# skyrizz_e32__se050-v1_1.net
KiCad netlist of a schematic drawn in EasyEDA Pro
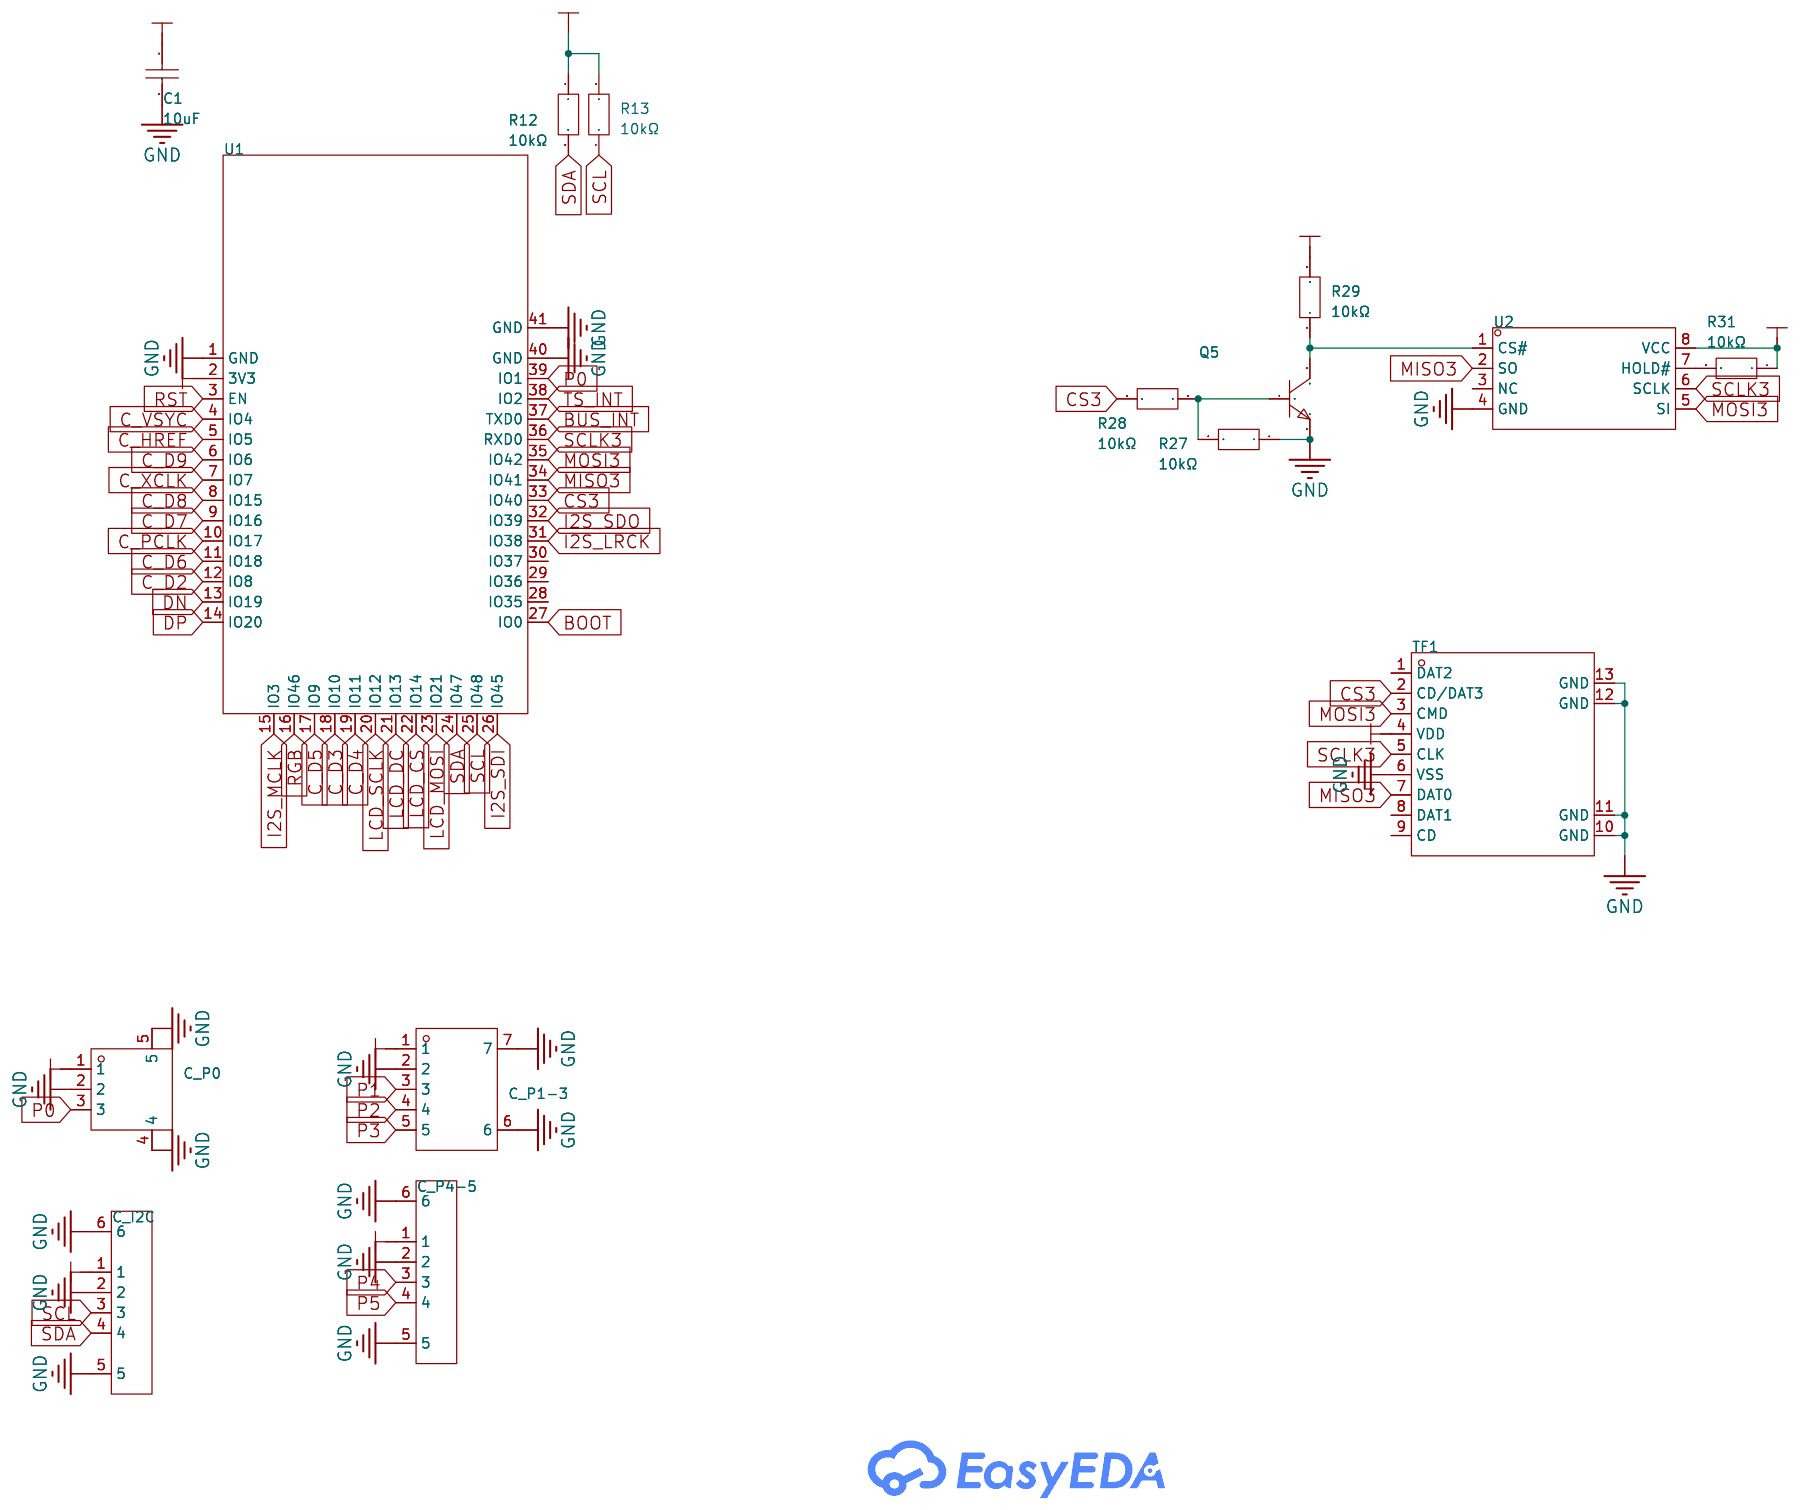
[diagram p0: MCU & MEMORY]
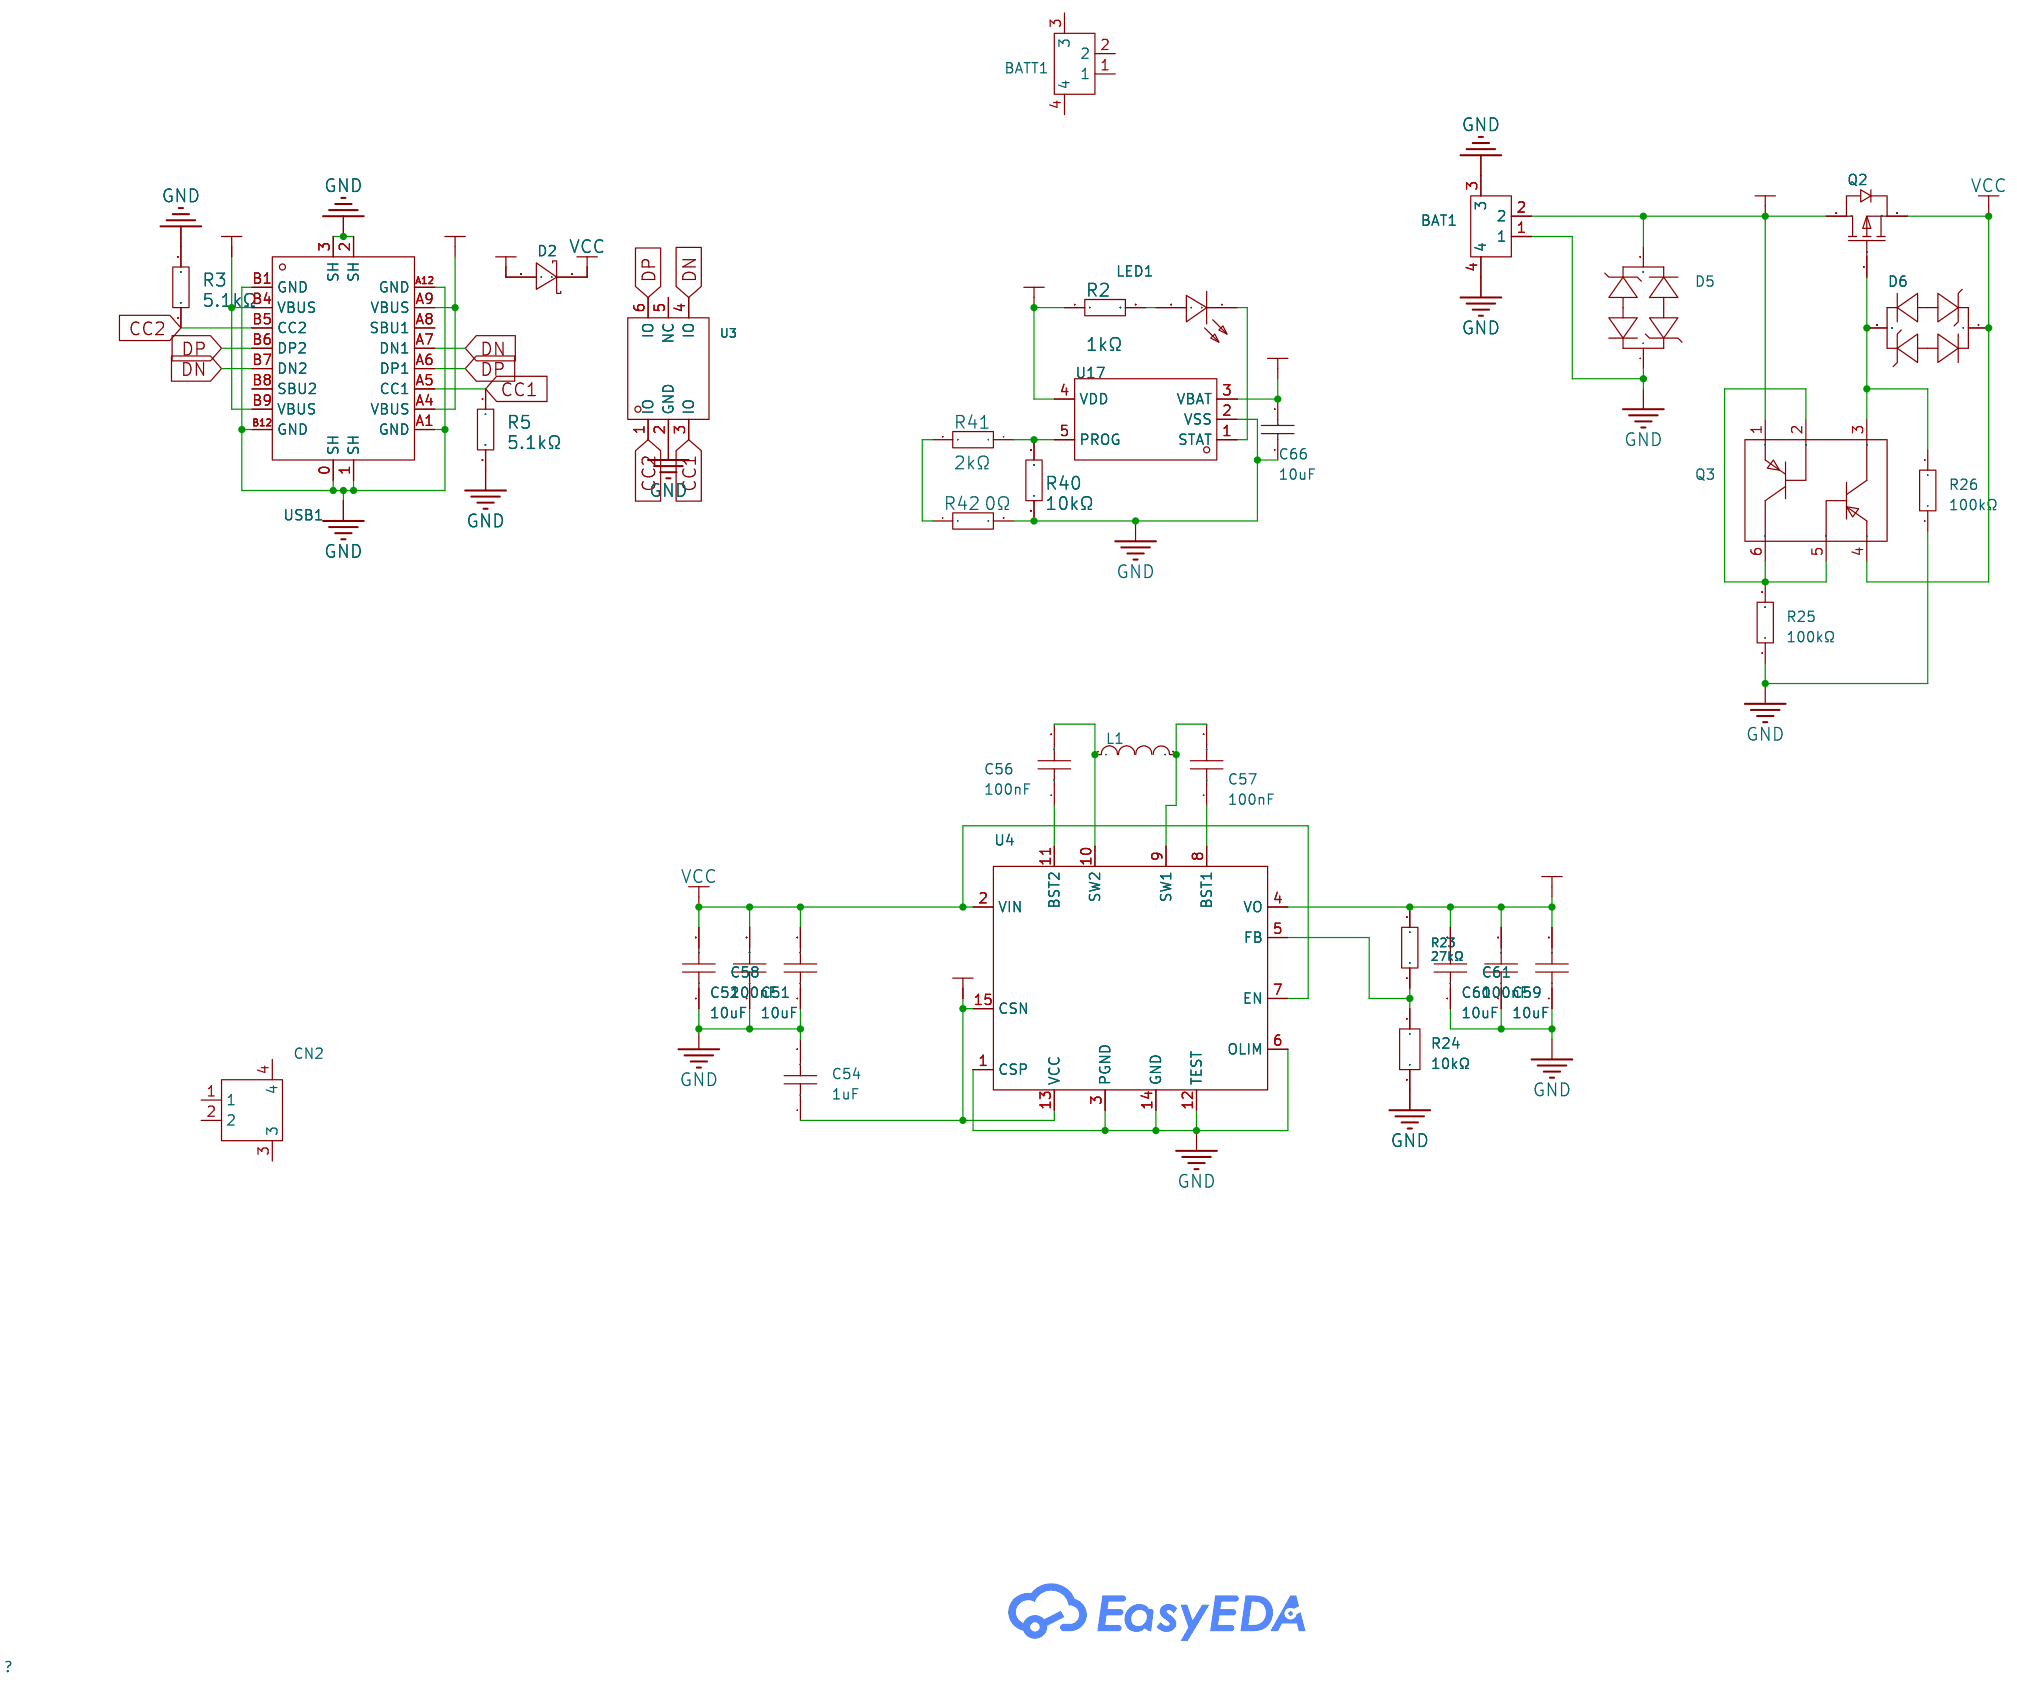
[diagram p1: POWER]
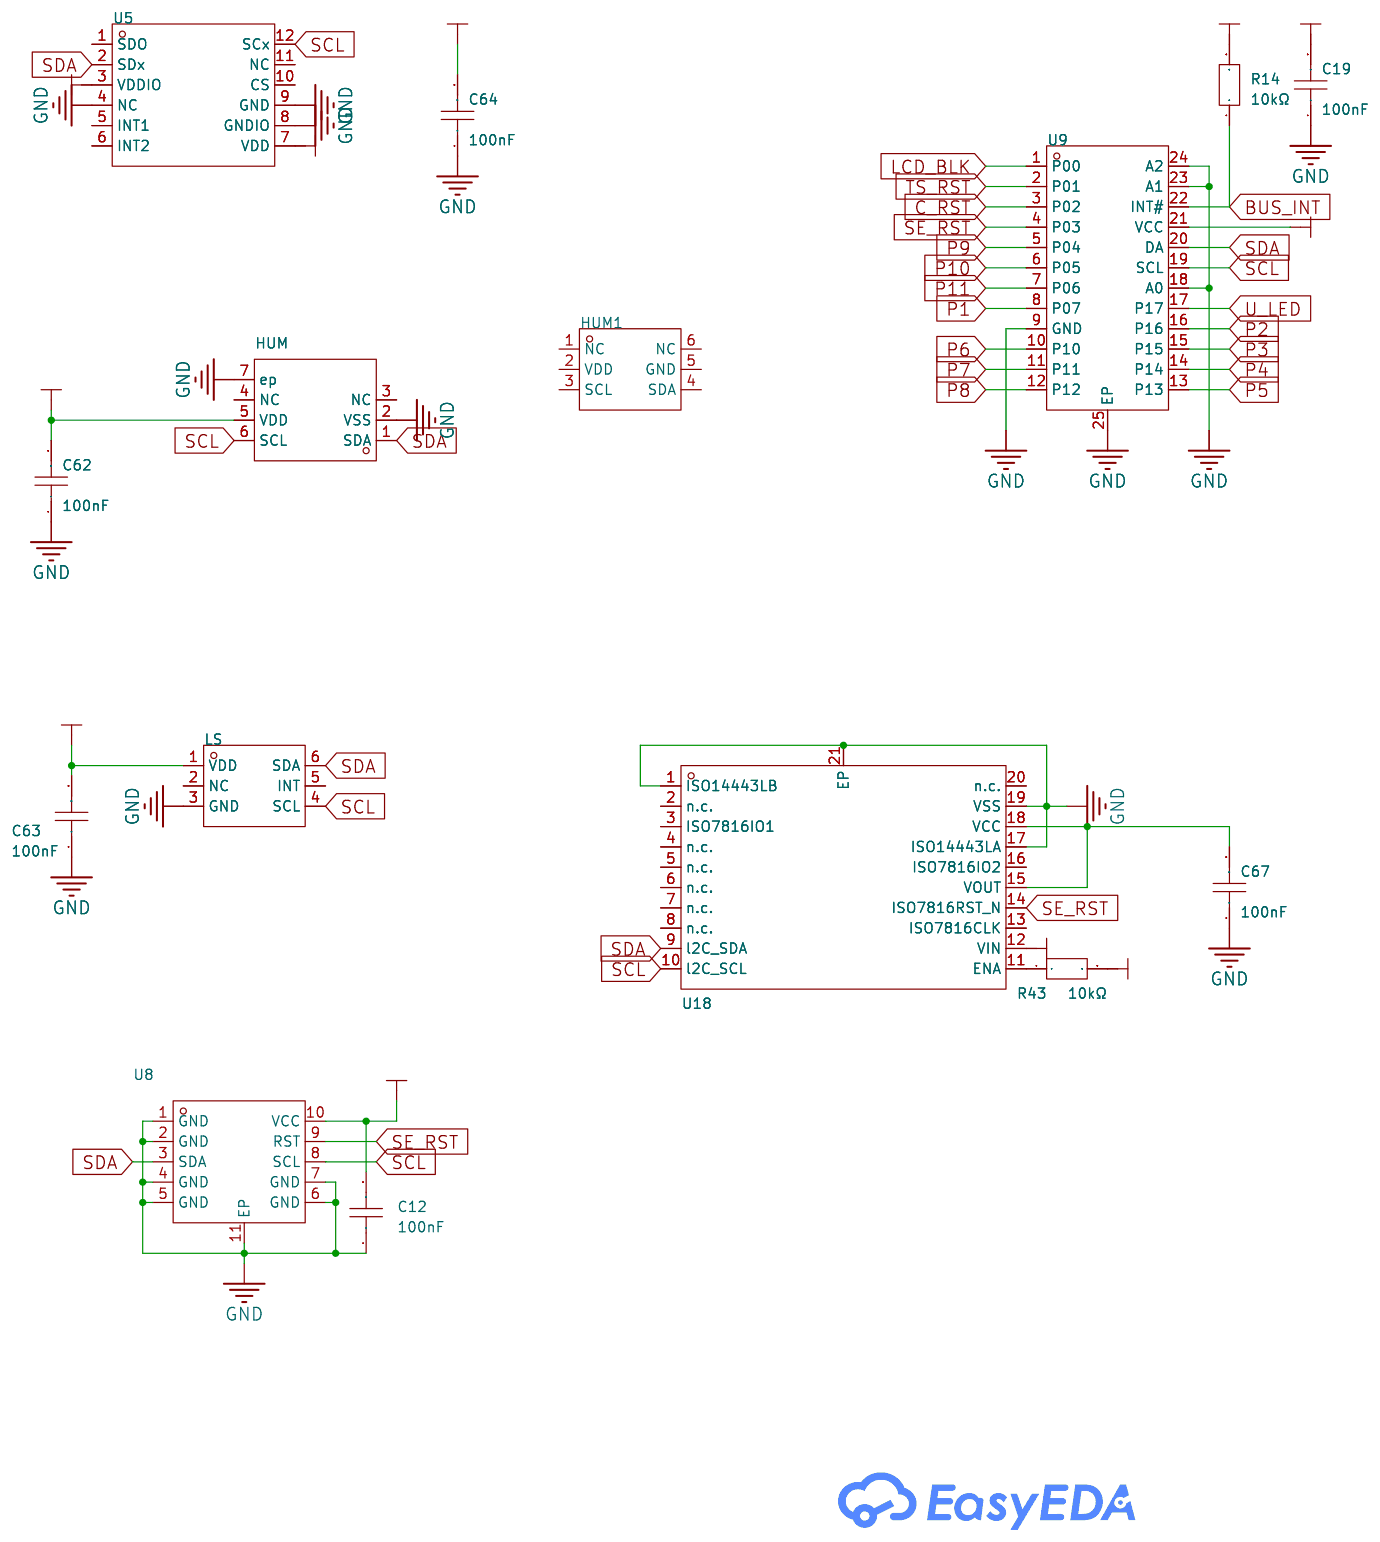
[diagram p2: SENSOR I2C]
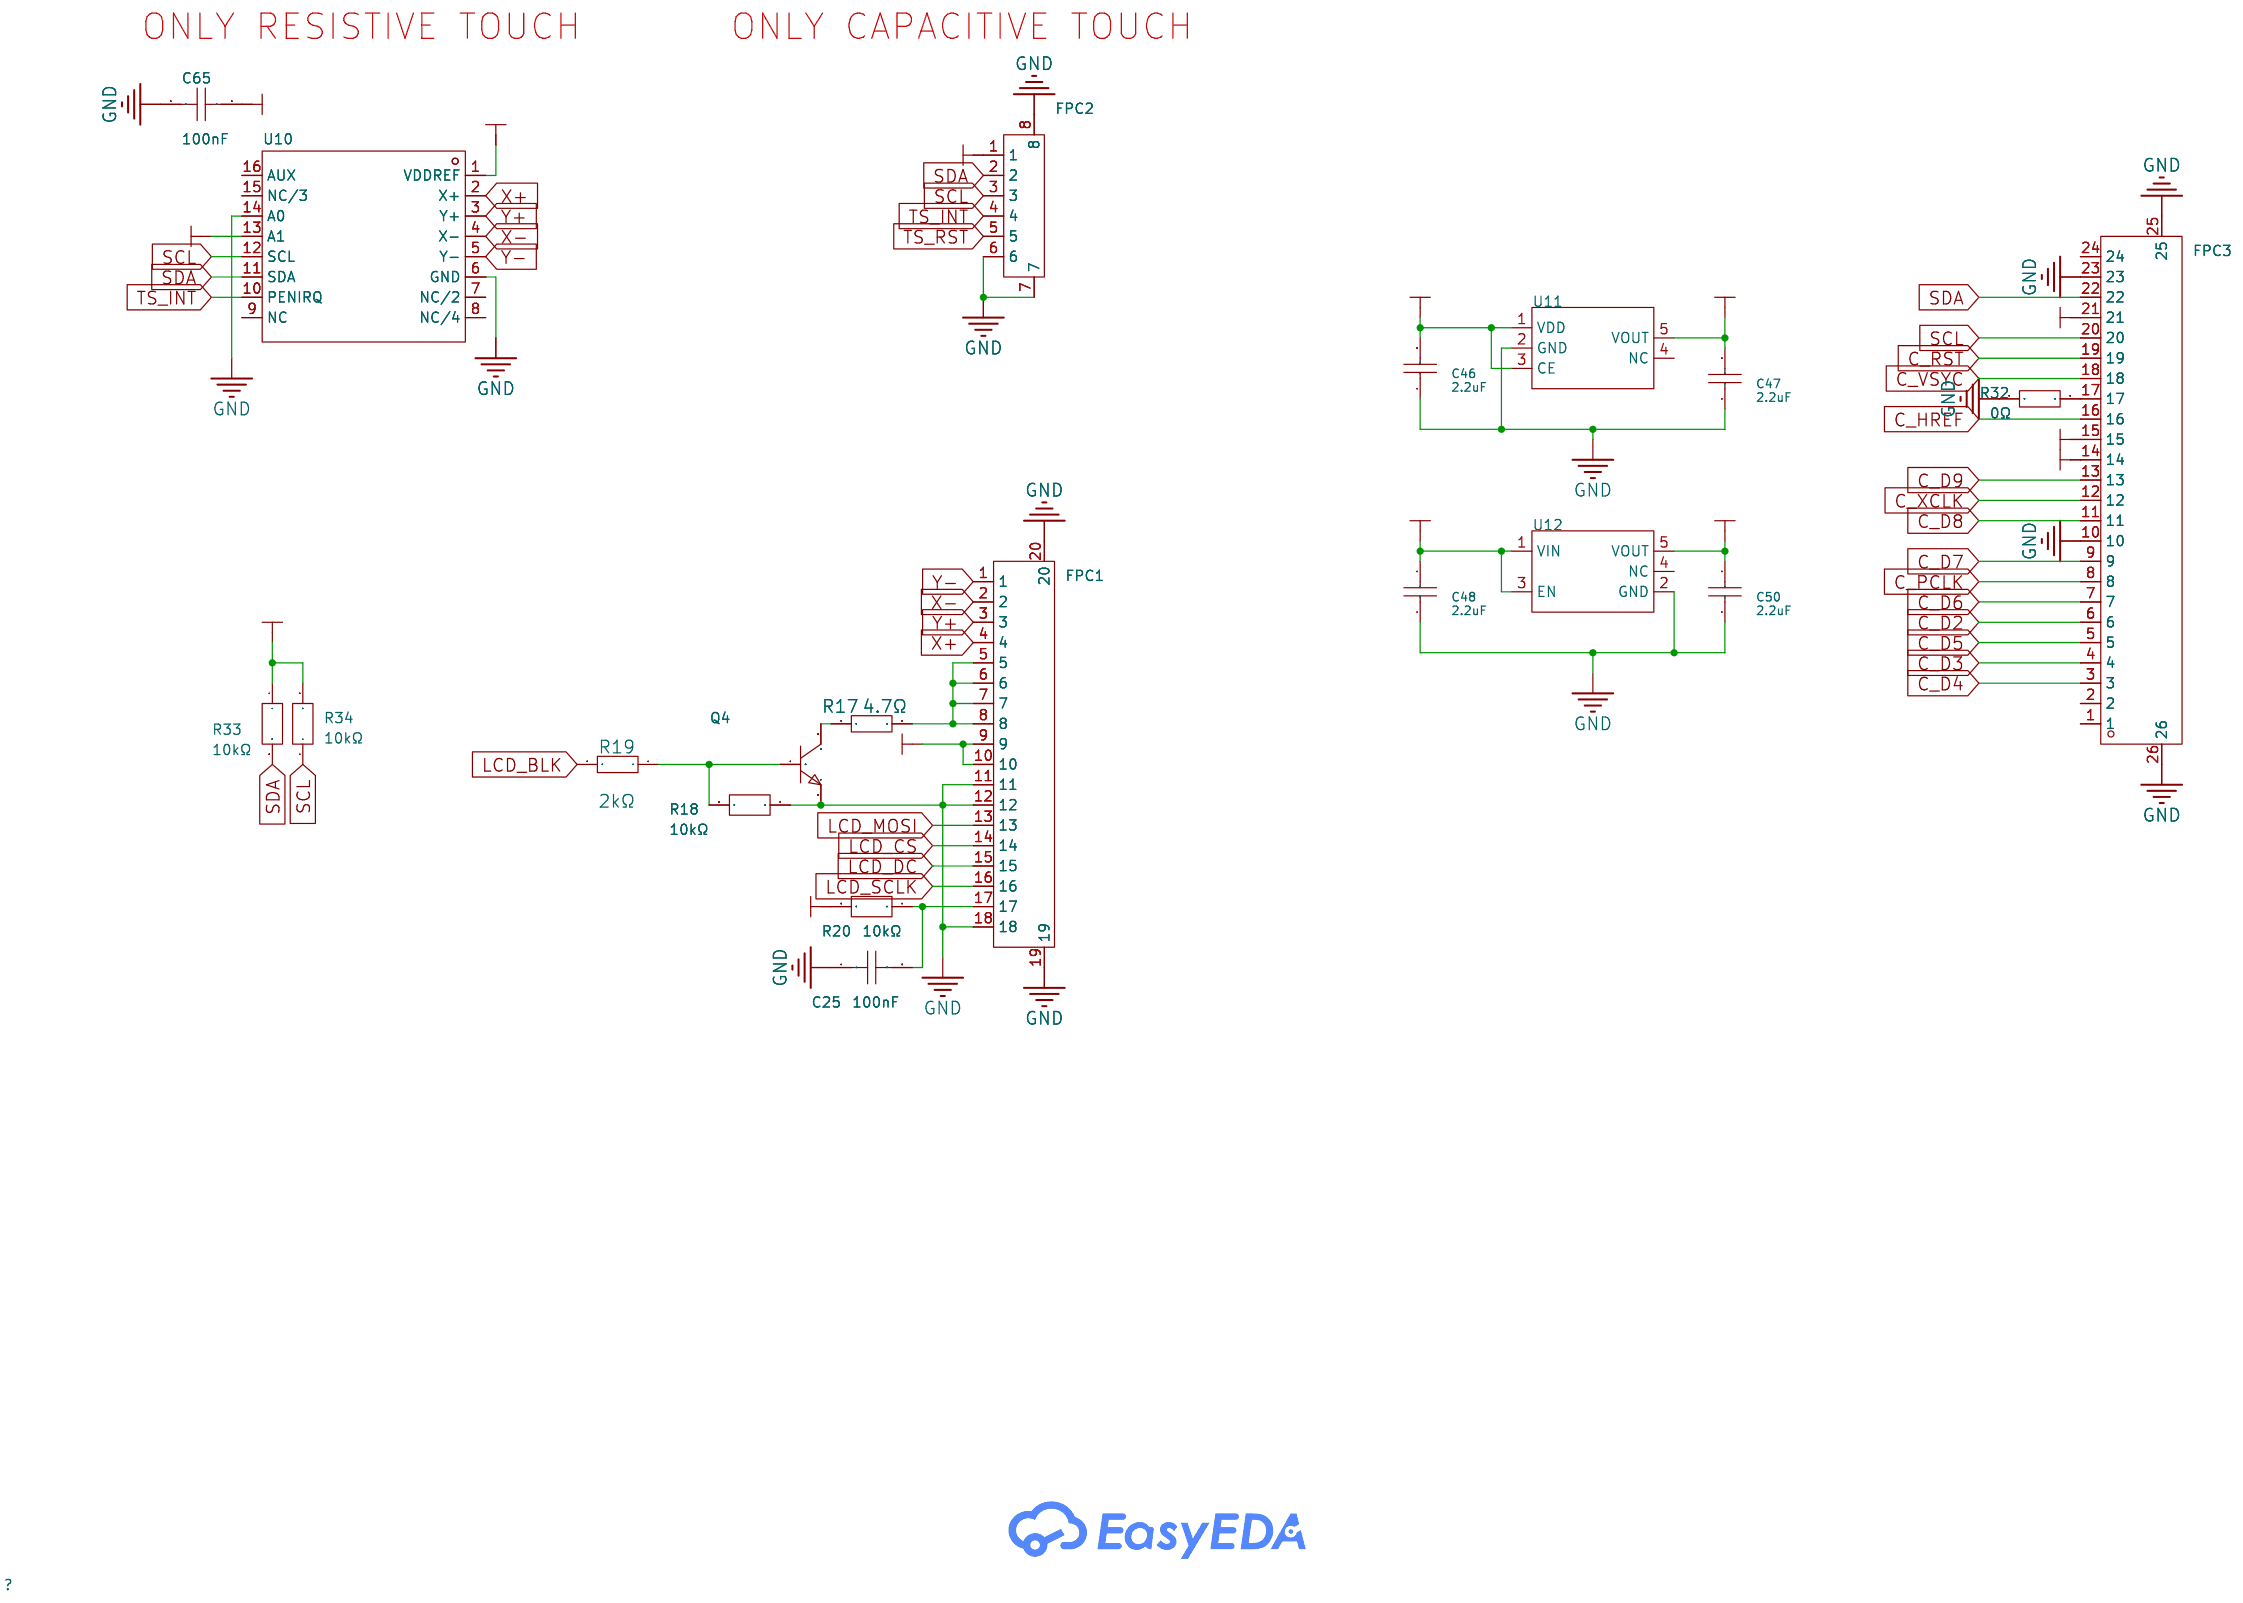
[diagram p3: LCD & CAM]
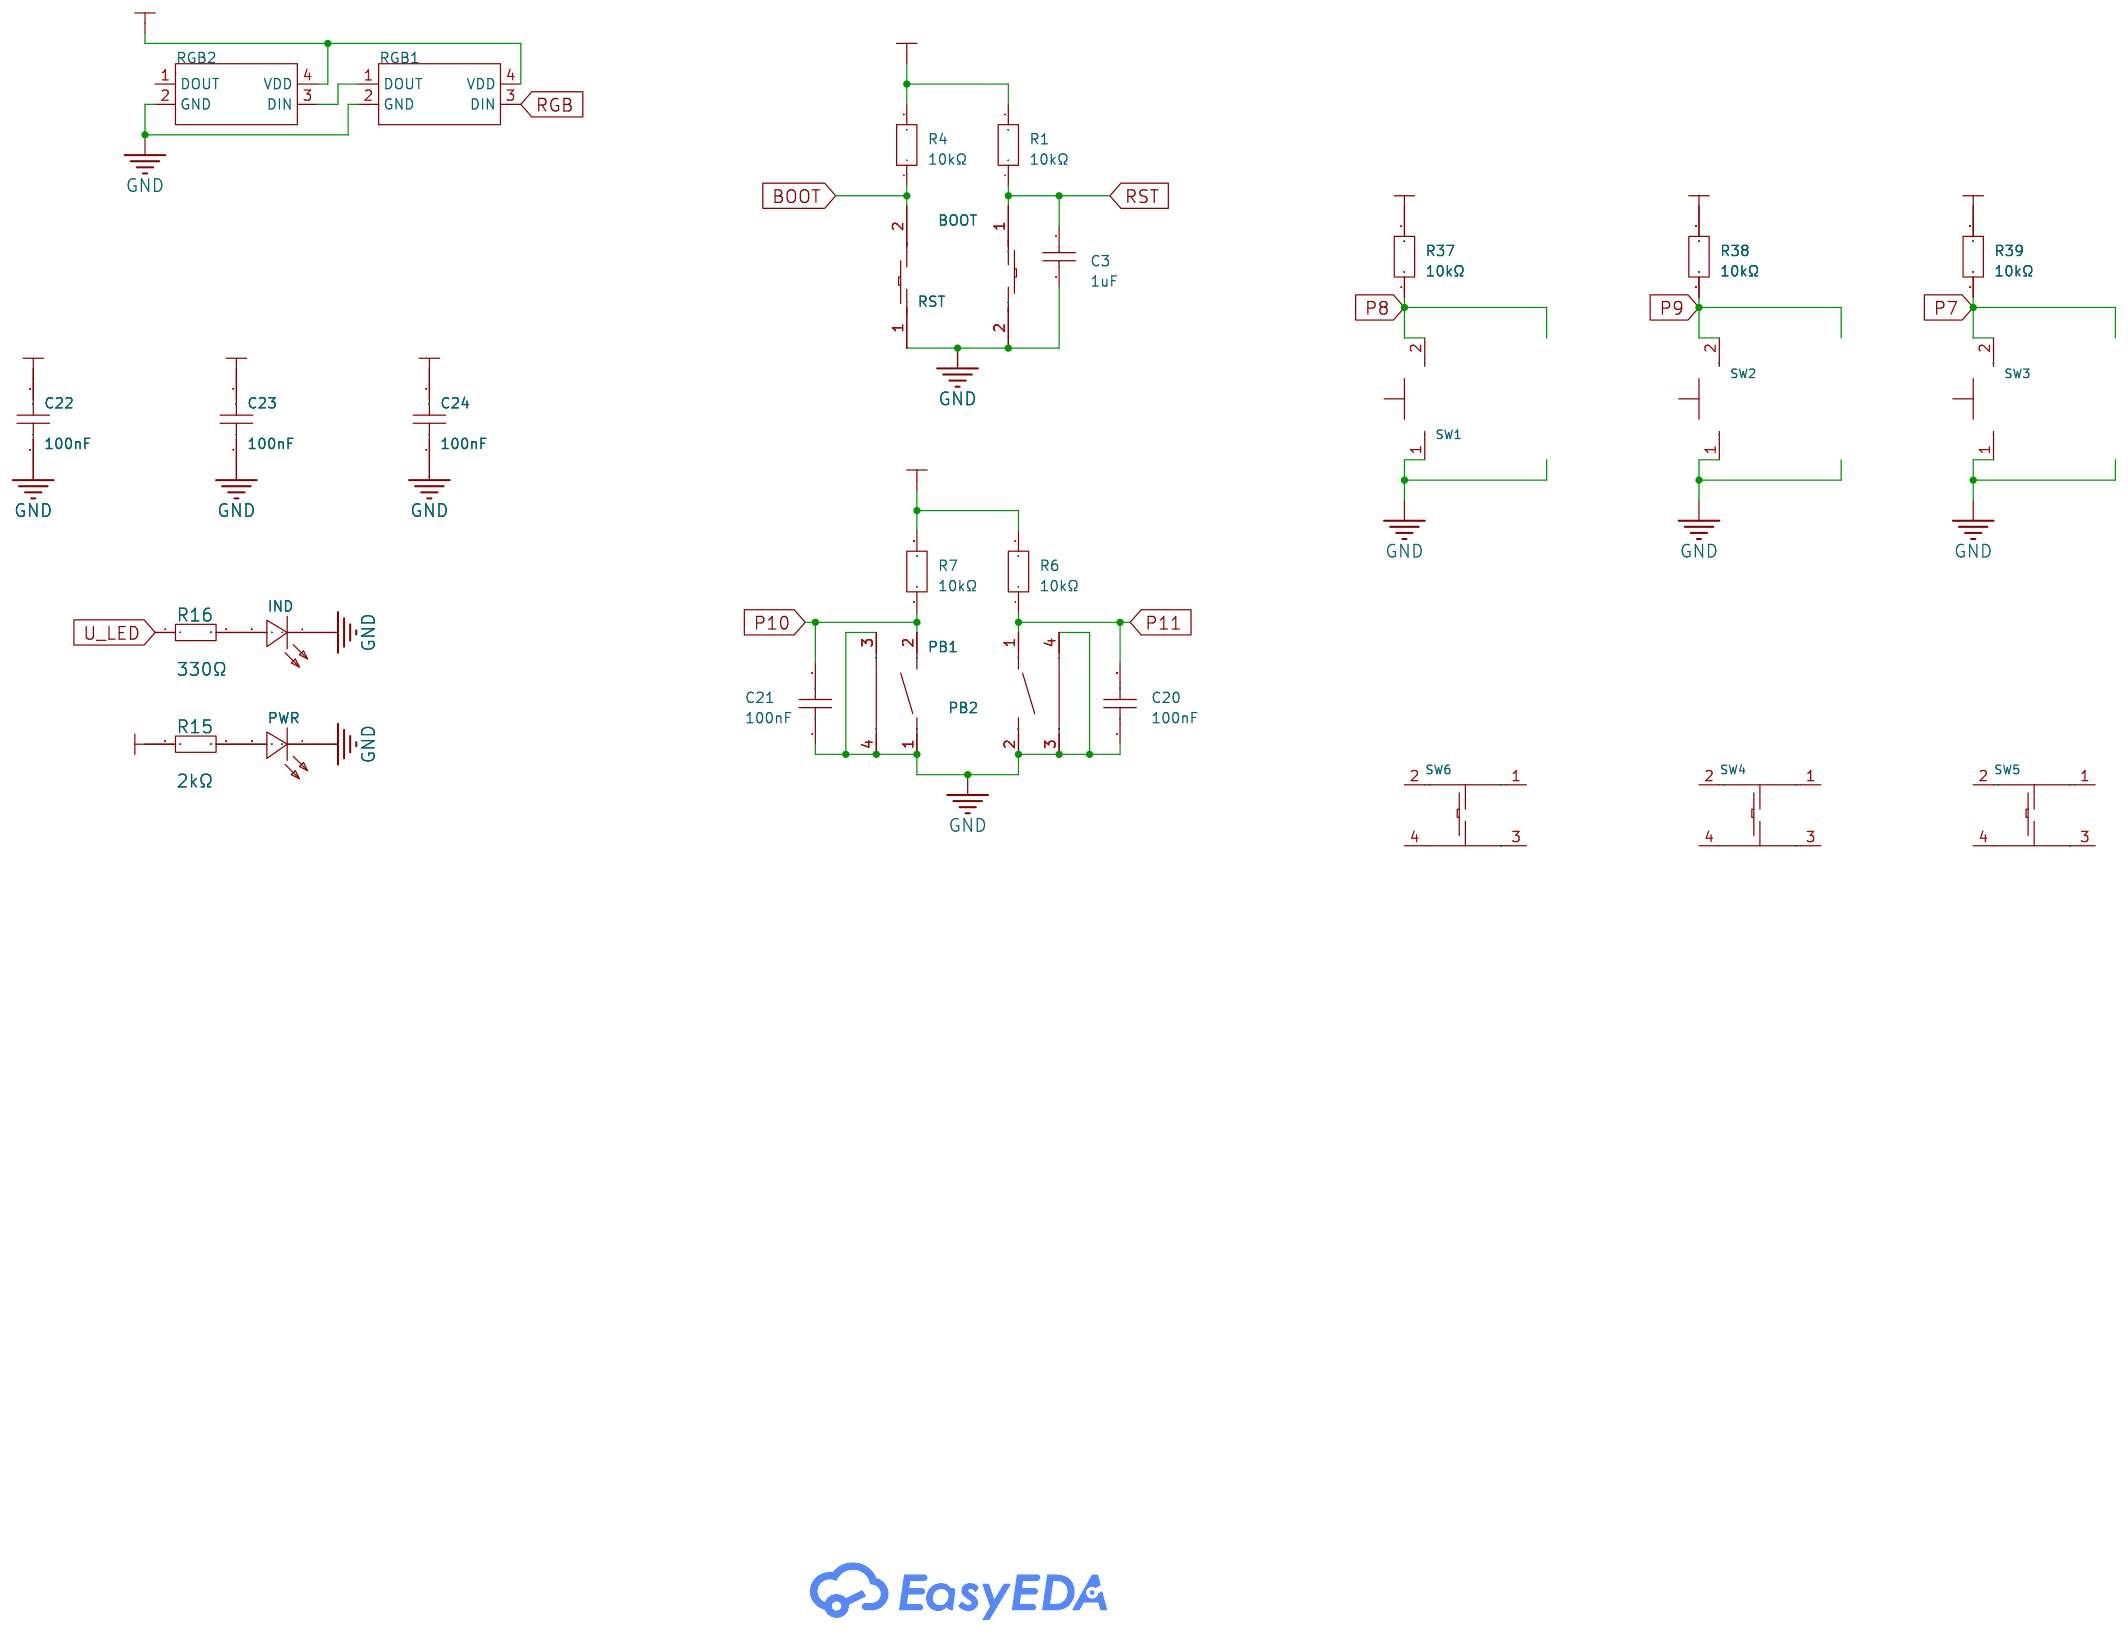
[diagram p4: BUTTON & IND]
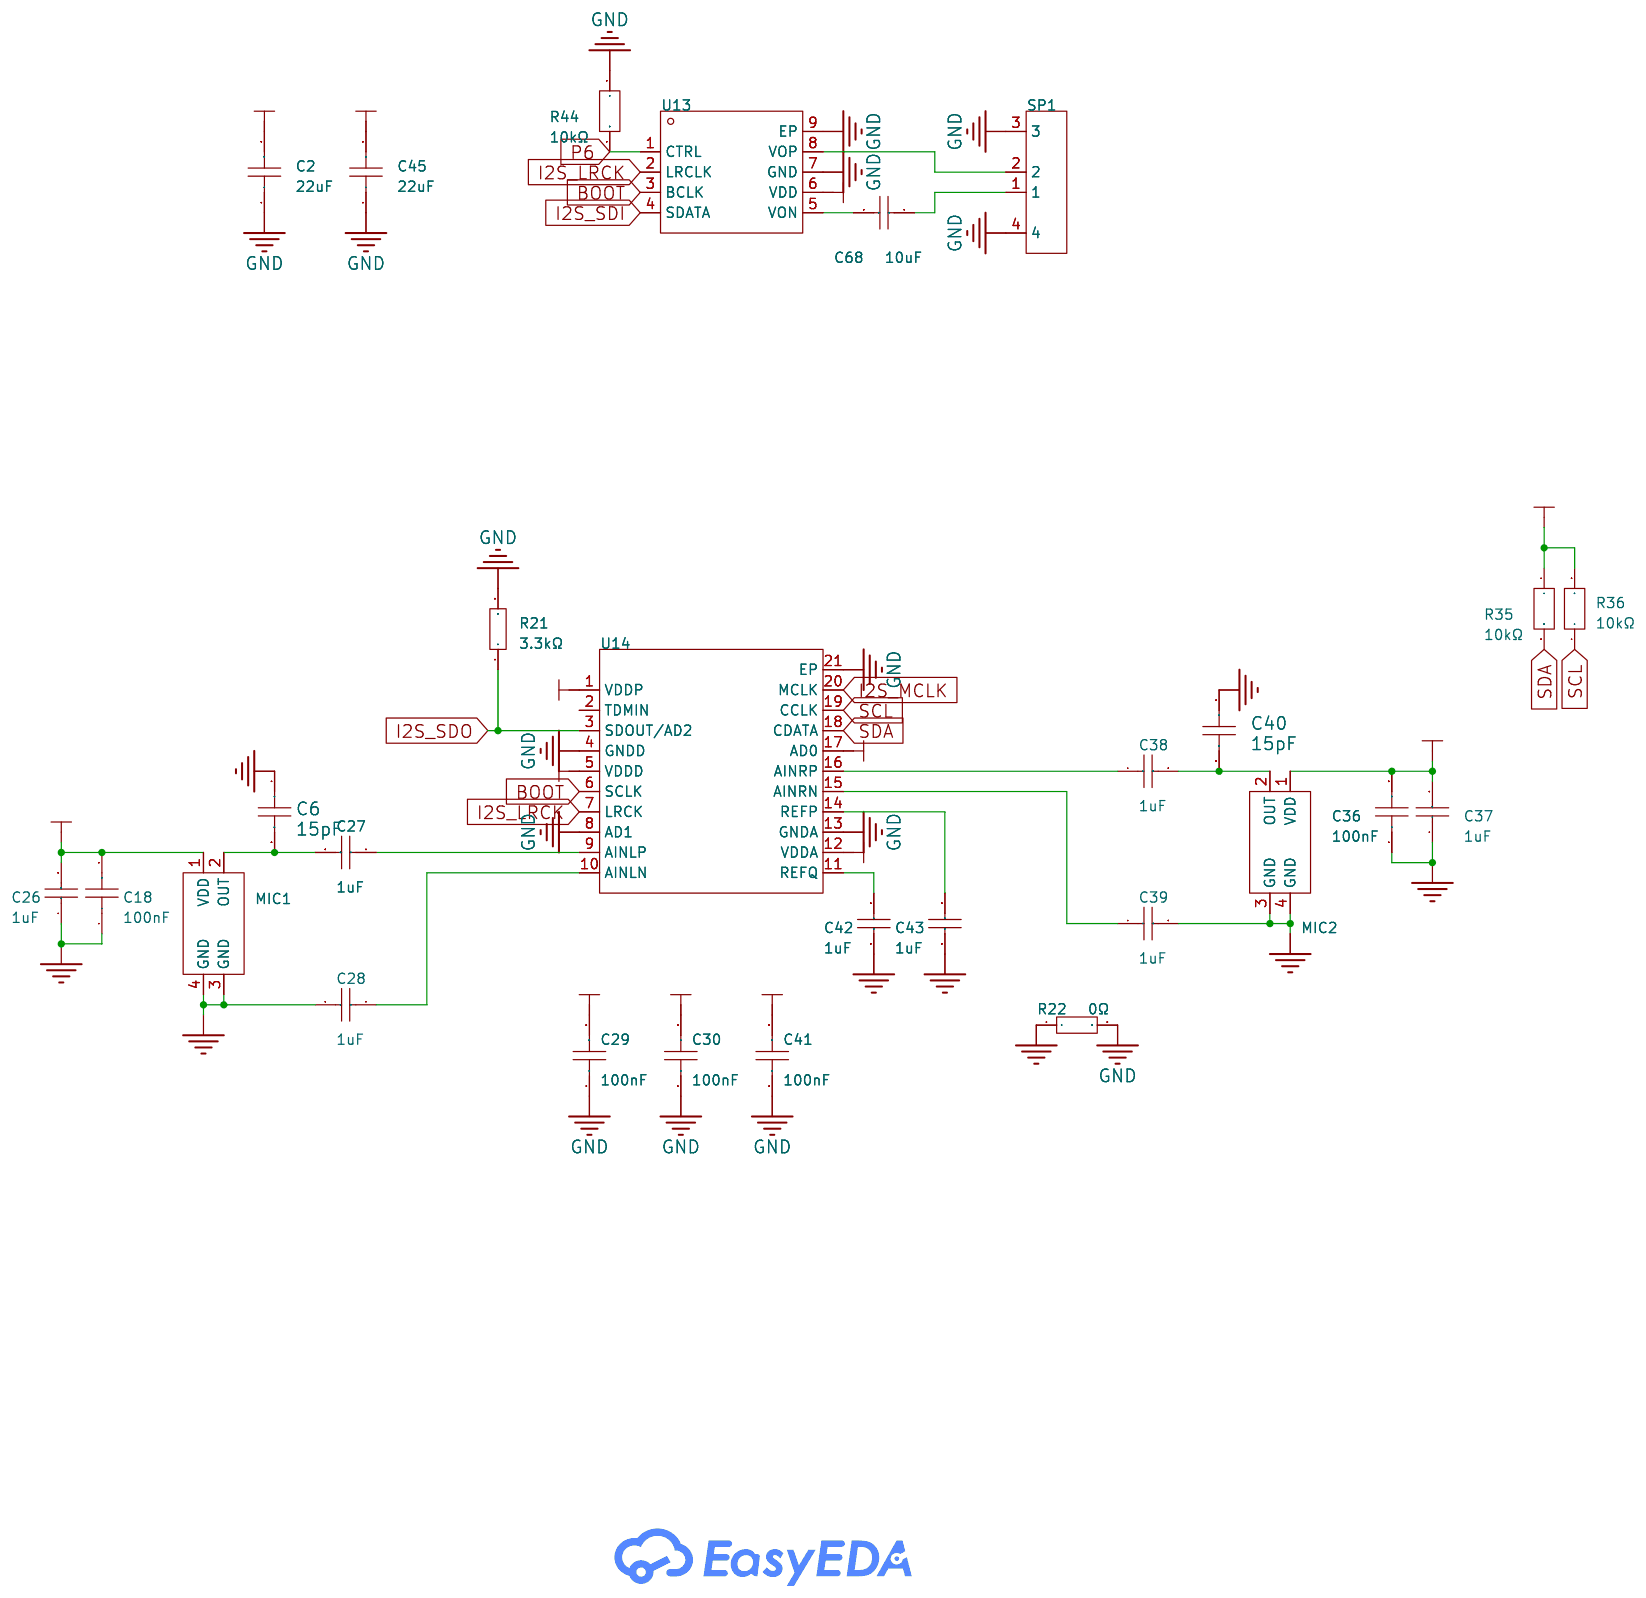
[diagram p5: MIC & SPEAKER]

(export (version "E")
  (design (tool "Eeschema 10.0.6"))
  (components
    (comp (ref "C1")
      (value "10uF")
      (description "Capacitance:10uF Tolerance:±20% Tolerance:±20% Voltage Rating:6.3V Temperature Coefficient:X5R")
      (fields
        (field (name "Manufacturer Part") "CL05A106MQ5NUNC")
        (field (name "Manufacturer") "SAMSUNG(三星)")
      )
      (libsource (lib "easyedapro") (part "CL05A106MQ5NUNC"))
    )
    (comp (ref "C_I2C")
      (value "SM04B-SRSS-TB(LF)(SN)")
      (footprint "easyedapro:CONN-SMD_4P-P1.00_SM04B-SRSS-TB-LF-SN")
      (fields (field (name "Manufacturer") "JST"))
      (libsource (lib "easyedapro") (part "SM04B-SRSS-TB (LF)(SN)"))
    )
    (comp (ref "C_P0")
      (value "SM03B-SRSS-TB(LF)(SN)")
      (footprint "easyedapro:CONN-SMD_SM03B-SRSS-TB-LF-SN-P")
      (fields (field (name "Manufacturer") "JST"))
      (libsource (lib "easyedapro") (part "SM03B-SRSS-TB(LF)(SN)(P)"))
    )
    (comp (ref "C_P1-3")
      (value "SM05B-SRSS-TB(LF)(SN)")
      (footprint "easyedapro:CONN-SMD_SM05B-SRSS-TB-LF-SN")
      (fields (field (name "Manufacturer") "JST"))
      (libsource (lib "easyedapro") (part "SM05B-SRSS-TB (LF)(SN)"))
    )
    (comp (ref "C_P4-5")
      (value "SM04B-SRSS-TB(LF)(SN)")
      (footprint "easyedapro:CONN-SMD_4P-P1.00_SM04B-SRSS-TB-LF-SN")
      (fields (field (name "Manufacturer") "JST"))
      (libsource (lib "easyedapro") (part "SM04B-SRSS-TB (LF)(SN)"))
    )
    (comp (ref "Q5")
      (value "MMBT3904")
      (footprint "easyedapro:SOT-23-3_L2.9-W1.3-P1.90-LS2.4-BR")
      (fields (field (name "Manufacturer") "DOWO(东沃)"))
      (libsource (lib "easyedapro") (part "MMBT3904_C22374713"))
    )
    (comp (ref "R12")
      (value "10kΩ")
      (footprint "easyedapro:R0201")
      (fields
        (field (name "Manufacturer Part") "0201WMF1002TEE")
        (field (name "Manufacturer") "UNI-ROYAL(厚声)")
      )
      (libsource (lib "easyedapro") (part "0201WMF1002TEE"))
    )
    (comp (ref "R13")
      (value "10kΩ")
      (footprint "easyedapro:R0201")
      (fields
        (field (name "Manufacturer Part") "0201WMF1002TEE")
        (field (name "Manufacturer") "UNI-ROYAL(厚声)")
      )
      (libsource (lib "easyedapro") (part "0201WMF1002TEE"))
    )
    (comp (ref "R27")
      (value "10kΩ")
      (footprint "easyedapro:R0201")
      (fields
        (field (name "Manufacturer Part") "0201WMF1002TEE")
        (field (name "Manufacturer") "UNI-ROYAL(厚声)")
      )
      (libsource (lib "easyedapro") (part "0201WMF1002TEE"))
    )
    (comp (ref "R28")
      (value "10kΩ")
      (footprint "easyedapro:R0201")
      (fields
        (field (name "Manufacturer Part") "0201WMF1002TEE")
        (field (name "Manufacturer") "UNI-ROYAL(厚声)")
      )
      (libsource (lib "easyedapro") (part "0201WMF1002TEE"))
    )
    (comp (ref "R29")
      (value "10kΩ")
      (footprint "easyedapro:R0201")
      (fields
        (field (name "Manufacturer Part") "0201WMF1002TEE")
        (field (name "Manufacturer") "UNI-ROYAL(厚声)")
      )
      (libsource (lib "easyedapro") (part "0201WMF1002TEE"))
    )
    (comp (ref "R31")
      (value "10kΩ")
      (footprint "easyedapro:R0201")
      (fields
        (field (name "Manufacturer Part") "0201WMF1002TEE")
        (field (name "Manufacturer") "UNI-ROYAL(厚声)")
      )
      (libsource (lib "easyedapro") (part "0201WMF1002TEE"))
    )
    (comp (ref "TF1")
      (value "TF-CARD H1.8")
      (footprint "easyedapro:TF-SMD_TF-CARD-H1.8")
      (fields (field (name "Manufacturer") "SHOU HAN(首韩)"))
      (libsource (lib "easyedapro") (part "TF-CARD H1.8"))
    )
    (comp (ref "U1")
      (value "ESP32-S3-WROOM-1-N16R8")
      (footprint "easyedapro:WIRELM-SMD_ESP32-S3-WROOM-1")
      (fields (field (name "Manufacturer") "ESPRESSIF(乐鑫)"))
      (libsource (lib "easyedapro") (part "ESP32-S3-WROOM-1(N16R8)"))
    )
    (comp (ref "U2")
      (value "GT30L24A3W")
      (footprint "easyedapro:SOIC-8_L5.3-W5.3-P1.27-LS8.0-BL")
      (fields (field (name "Manufacturer") "GENITOP(高通)"))
      (libsource (lib "easyedapro") (part "GT30L24A3W"))
    )
    (comp (ref "BAT1")
      (value "MX1.25mm-2P-WT")
      (footprint "easyedapro:CONN-SMD_MX1.25-2P-WT")
      (fields (field (name "Manufacturer") "LXWCONN(连兴旺电子)"))
      (libsource (lib "easyedapro") (part "MX1.25MM-2P-WT"))
    )
    (comp (ref "BATT1")
      (value "PH-2P卧贴")
      (footprint "easyedapro:CONN-SMD_2P-P2.00_PH2.0-SPWB")
      (fields (field (name "Manufacturer") "BOOMELE(博穆精密)"))
      (libsource (lib "easyedapro") (part "PH2.0-2PWB"))
    )
    (comp (ref "C51")
      (value "10uF")
      (footprint "easyedapro:C0402")
      (description "Capacitance:10uF Tolerance:±20% Tolerance:±20% Voltage Rating:10V Temperature Coefficient:X5R")
      (fields
        (field (name "Manufacturer Part") "GRM155R61A106ME44D")
        (field (name "Manufacturer") "muRata(村田)")
      )
      (libsource (lib "easyedapro") (part "GRM155R61A106ME44D"))
    )
    (comp (ref "C52")
      (value "10uF")
      (footprint "easyedapro:C0402")
      (description "Capacitance:10uF Tolerance:±20% Tolerance:±20% Voltage Rating:10V Temperature Coefficient:X5R")
      (fields
        (field (name "Manufacturer Part") "GRM155R61A106ME44D")
        (field (name "Manufacturer") "muRata(村田)")
      )
      (libsource (lib "easyedapro") (part "GRM155R61A106ME44D"))
    )
    (comp (ref "C54")
      (value "1uF")
      (footprint "easyedapro:C0402")
      (description "Capacitance:1uF Tolerance:±10% Tolerance:±10% Voltage Rating:25V Temperature Coefficient:X5R")
      (fields
        (field (name "Manufacturer Part") "CL05A105KA5NQNC")
        (field (name "Manufacturer") "SAMSUNG(三星)")
      )
      (libsource (lib "easyedapro") (part "CL05A105KA5NQNC"))
    )
    (comp (ref "C56")
      (value "100nF")
      (footprint "easyedapro:C0402")
      (description "Capacitance:100nF Tolerance:±10% Tolerance:±10% Voltage Rating:16V Temperature Coefficient:X7R")
      (fields
        (field (name "Manufacturer Part") "CL05B104KO5NNNC")
        (field (name "Manufacturer") "SAMSUNG(三星)")
      )
      (libsource (lib "easyedapro") (part "CL05B104KO5NNNC"))
    )
    (comp (ref "C57")
      (value "100nF")
      (footprint "easyedapro:C0402")
      (description "Capacitance:100nF Tolerance:±10% Tolerance:±10% Voltage Rating:16V Temperature Coefficient:X7R")
      (fields
        (field (name "Manufacturer Part") "CL05B104KO5NNNC")
        (field (name "Manufacturer") "SAMSUNG(三星)")
      )
      (libsource (lib "easyedapro") (part "CL05B104KO5NNNC"))
    )
    (comp (ref "C58")
      (value "100nF")
      (footprint "easyedapro:C0402")
      (description "Capacitance:100nF Tolerance:±10% Tolerance:±10% Voltage Rating:16V Temperature Coefficient:X7R")
      (fields
        (field (name "Manufacturer Part") "CL05B104KO5NNNC")
        (field (name "Manufacturer") "SAMSUNG(三星)")
      )
      (libsource (lib "easyedapro") (part "CL05B104KO5NNNC"))
    )
    (comp (ref "C59")
      (value "10uF")
      (footprint "easyedapro:C0402")
      (description "Capacitance:10uF Tolerance:±20% Tolerance:±20% Voltage Rating:10V Temperature Coefficient:X5R")
      (fields
        (field (name "Manufacturer Part") "GRM155R61A106ME44D")
        (field (name "Manufacturer") "muRata(村田)")
      )
      (libsource (lib "easyedapro") (part "GRM155R61A106ME44D"))
    )
    (comp (ref "C60")
      (value "10uF")
      (footprint "easyedapro:C0402")
      (description "Capacitance:10uF Tolerance:±20% Tolerance:±20% Voltage Rating:10V Temperature Coefficient:X5R")
      (fields
        (field (name "Manufacturer Part") "GRM155R61A106ME44D")
        (field (name "Manufacturer") "muRata(村田)")
      )
      (libsource (lib "easyedapro") (part "GRM155R61A106ME44D"))
    )
    (comp (ref "C61")
      (value "100nF")
      (footprint "easyedapro:C0402")
      (description "Capacitance:100nF Tolerance:±10% Tolerance:±10% Voltage Rating:16V Temperature Coefficient:X7R")
      (fields
        (field (name "Manufacturer Part") "CL05B104KO5NNNC")
        (field (name "Manufacturer") "SAMSUNG(三星)")
      )
      (libsource (lib "easyedapro") (part "CL05B104KO5NNNC"))
    )
    (comp (ref "C66")
      (value "10uF")
      (description "Capacitance:10uF Tolerance:±20% Tolerance:±20% Voltage Rating:6.3V Temperature Coefficient:X5R")
      (fields
        (field (name "Manufacturer Part") "CL05A106MQ5NUNC")
        (field (name "Manufacturer") "SAMSUNG(三星)")
      )
      (libsource (lib "easyedapro") (part "CL05A106MQ5NUNC"))
    )
    (comp (ref "CN2")
      (value "MX1.25mm-2P-LT")
      (footprint "easyedapro:CONN-SMD_2P-P1.25_WS32021-S0471")
      (fields (field (name "Manufacturer") "LXWCONN(连兴旺电子)"))
      (libsource (lib "easyedapro") (part "MX1.25MM-2P-LT"))
    )
    (comp (ref "D2")
      (value "SS34")
      (footprint "easyedapro:SMA_L4.3-W2.6-LS5.2-RD")
      (fields (field (name "Manufacturer") "MDD(辰达半导体)"))
      (libsource (lib "easyedapro") (part "SS34_C8678"))
    )
    (comp (ref "D5")
      (value "PTVSUC3D5VB")
      (footprint "easyedapro:SOD-323_L1.8-W1.3-LS2.5-BI")
      (fields (field (name "Manufacturer") "Prisemi(芯导)"))
      (libsource (lib "easyedapro") (part "PTVSUC3D5VB"))
    )
    (comp (ref "D6")
      (value "PTVSUC3D5VB")
      (footprint "easyedapro:SOD-323_L1.8-W1.3-LS2.5-BI")
      (fields (field (name "Manufacturer") "Prisemi(芯导)"))
      (libsource (lib "easyedapro") (part "PTVSUC3D5VB"))
    )
    (comp (ref "L1")
      (value "2.2uH")
      (footprint "easyedapro:IND-SMD_L3.5-W3.0")
      (fields (field (name "Manufacturer Part") "SM3521-2R2MT") (field (name "Manufacturer") "SXN(顺翔诺)"))
      (libsource (lib "easyedapro") (part "SM3521-2R2MT"))
    )
    (comp (ref "LED1")
      (value "KT-0603R")
      (fields (field (name "Manufacturer") "KENTO"))
      (libsource (lib "easyedapro") (part "KT-0603R"))
    )
    (comp (ref "Q2")
      (value "AO3401A")
      (fields (field (name "Manufacturer") "AOS"))
      (libsource (lib "easyedapro") (part "AO3401A"))
    )
    (comp (ref "Q3")
      (value "BCM857BS")
      (footprint "easyedapro:SOT-363_L2.1-W1.3-P0.65-LS2.3-BL")
      (fields (field (name "Manufacturer") "FUXINSEMI(富芯森美)"))
      (libsource (lib "easyedapro") (part "BCM857BS"))
    )
    (comp (ref "R2")
      (value "1kΩ")
      (footprint "easyedapro:R0201")
      (fields
        (field (name "Manufacturer Part") "0201WMF1001TEE")
        (field (name "Manufacturer") "UNI-ROYAL(厚声)")
      )
      (libsource (lib "easyedapro") (part "0201WMF1001TEE"))
    )
    (comp (ref "R3")
      (value "5.1kΩ")
      (footprint "easyedapro:R0201")
      (fields
        (field (name "Manufacturer Part") "0201WMF5101TEE")
        (field (name "Manufacturer") "UNI-ROYAL(厚声)")
      )
      (libsource (lib "easyedapro") (part "0201WMF5101TEE"))
    )
    (comp (ref "R5")
      (value "5.1kΩ")
      (footprint "easyedapro:R0201")
      (fields
        (field (name "Manufacturer Part") "0201WMF5101TEE")
        (field (name "Manufacturer") "UNI-ROYAL(厚声)")
      )
      (libsource (lib "easyedapro") (part "0201WMF5101TEE"))
    )
    (comp (ref "R23")
      (value "27kΩ")
      (footprint "easyedapro:R0201")
      (fields
        (field (name "Manufacturer Part") "0201WMF2702TEE")
        (field (name "Manufacturer") "UNI-ROYAL(厚声)")
      )
      (libsource (lib "easyedapro") (part "0201WMF2702TEE"))
    )
    (comp (ref "R24")
      (value "10kΩ")
      (footprint "easyedapro:R0201")
      (fields
        (field (name "Manufacturer Part") "0201WMF1002TEE")
        (field (name "Manufacturer") "UNI-ROYAL(厚声)")
      )
      (libsource (lib "easyedapro") (part "0201WMF1002TEE"))
    )
    (comp (ref "R25")
      (value "100kΩ")
      (footprint "easyedapro:R0201")
      (fields
        (field (name "Manufacturer Part") "0201WMF1003TEE")
        (field (name "Manufacturer") "UNI-ROYAL(厚声)")
      )
      (libsource (lib "easyedapro") (part "0201WMF1003TEE"))
    )
    (comp (ref "R26")
      (value "100kΩ")
      (footprint "easyedapro:R0201")
      (fields
        (field (name "Manufacturer Part") "0201WMF1003TEE")
        (field (name "Manufacturer") "UNI-ROYAL(厚声)")
      )
      (libsource (lib "easyedapro") (part "0201WMF1003TEE"))
    )
    (comp (ref "R40")
      (value "10kΩ")
      (footprint "easyedapro:R0201")
      (fields
        (field (name "Manufacturer Part") "0201WMF1002TEE")
        (field (name "Manufacturer") "UNI-ROYAL(厚声)")
      )
      (libsource (lib "easyedapro") (part "0201WMF1001TEE"))
    )
    (comp (ref "R41")
      (value "2kΩ")
      (footprint "easyedapro:R0201")
      (fields
        (field (name "Manufacturer Part") "0201WMF2001TEE")
        (field (name "Manufacturer") "UNI-ROYAL(厚声)")
      )
      (libsource (lib "easyedapro") (part "0201WMF1001TEE"))
    )
    (comp (ref "R42")
      (value "0Ω")
      (footprint "easyedapro:R0402")
      (fields
        (field (name "Manufacturer Part") "0402WGF0000TCE")
        (field (name "Manufacturer") "UNI-ROYAL(厚声)")
      )
      (libsource (lib "easyedapro") (part "0402WGF0000TCE"))
    )
    (comp (ref "U3")
      (value "PUSB2X4Y")
      (footprint "easyedapro:SOT-363-6_L2.0-W1.3-P0.65-LS2.1-BL")
      (fields (field (name "Manufacturer") "TECH PUBLIC(台舟)"))
      (libsource (lib "easyedapro") (part "PUSB2X4Y"))
    )
    (comp (ref "U4")
      (value "JW3651QFNE#TRPBF")
      (footprint "easyedapro:QFN-15_L4.0-W3.0_JW3655E")
      (fields (field (name "Manufacturer") "Joulwatt(杰华特)"))
      (libsource (lib "easyedapro") (part "JW3651QFNE#TRPBF"))
    )
    (comp (ref "U17")
      (value "MCP73831T-2ACI/OT")
      (footprint "easyedapro:SOT-23-5_L3.0-W1.7-P0.95-LS2.8-BL")
      (fields (field (name "Manufacturer") "MICROCHIP(美国微芯)"))
      (libsource (lib "easyedapro") (part "MCP73831T-2ACI/OT"))
    )
    (comp (ref "USB1")
      (value "USB-TYPE-C-018")
      (footprint "easyedapro:USB-C_SMD-TYPE-C-31-M-12")
      (fields (field (name "Manufacturer") "DEALON(德艺隆)"))
      (libsource (lib "easyedapro") (part "USB-TYPE-C-018"))
    )
    (comp (ref "C12")
      (value "100nF")
      (footprint "easyedapro:C0201")
      (description "Capacitance:100nF Tolerance:±10% Tolerance:±10% Voltage Rating:10V Temperature Coefficient:X5R")
      (fields
        (field (name "Manufacturer Part") "CL03A104KP3NNNC")
        (field (name "Manufacturer") "SAMSUNG(三星)")
      )
      (libsource (lib "easyedapro") (part "CL03A104KP3NNNC"))
    )
    (comp (ref "C19")
      (value "100nF")
      (footprint "easyedapro:C0201")
      (description "Capacitance:100nF Tolerance:±10% Tolerance:±10% Voltage Rating:10V Temperature Coefficient:X5R")
      (fields
        (field (name "Manufacturer Part") "CL03A104KP3NNNC")
        (field (name "Manufacturer") "SAMSUNG(三星)")
      )
      (libsource (lib "easyedapro") (part "CL03A104KP3NNNC"))
    )
    (comp (ref "C62")
      (value "100nF")
      (footprint "easyedapro:C0201")
      (description "Capacitance:100nF Tolerance:±10% Tolerance:±10% Voltage Rating:10V Temperature Coefficient:X5R")
      (fields
        (field (name "Manufacturer Part") "CL03A104KP3NNNC")
        (field (name "Manufacturer") "SAMSUNG(三星)")
      )
      (libsource (lib "easyedapro") (part "CL03A104KP3NNNC"))
    )
    (comp (ref "C63")
      (value "100nF")
      (footprint "easyedapro:C0201")
      (description "Capacitance:100nF Tolerance:±10% Tolerance:±10% Voltage Rating:10V Temperature Coefficient:X5R")
      (fields
        (field (name "Manufacturer Part") "CL03A104KP3NNNC")
        (field (name "Manufacturer") "SAMSUNG(三星)")
      )
      (libsource (lib "easyedapro") (part "CL03A104KP3NNNC"))
    )
    (comp (ref "C64")
      (value "100nF")
      (footprint "easyedapro:C0201")
      (description "Capacitance:100nF Tolerance:±10% Tolerance:±10% Voltage Rating:10V Temperature Coefficient:X5R")
      (fields
        (field (name "Manufacturer Part") "CL03A104KP3NNNC")
        (field (name "Manufacturer") "SAMSUNG(三星)")
      )
      (libsource (lib "easyedapro") (part "CL03A104KP3NNNC"))
    )
    (comp (ref "C67")
      (value "100nF")
      (footprint "easyedapro:C0201")
      (description "Capacitance:100nF Tolerance:±10% Tolerance:±10% Voltage Rating:10V Temperature Coefficient:X5R")
      (fields
        (field (name "Manufacturer Part") "CL03A104KP3NNNC")
        (field (name "Manufacturer") "SAMSUNG(三星)")
      )
      (libsource (lib "easyedapro") (part "CL03A104KP3NNNC"))
    )
    (comp (ref "HUM")
      (value "SHT20-TR-1.5KS")
      (footprint "easyedapro:DFN-6_L3.0-W3.0-P0.95-TR-EP")
      (fields (field (name "Manufacturer") "Sensirion(瑞士盛思锐)"))
      (libsource (lib "easyedapro") (part "SHT20"))
    )
    (comp (ref "HUM1")
      (value "AHT20")
      (footprint "easyedapro:SENSOR-SMD_L3.0-W3.0-P1.00-BR")
      (fields (field (name "Manufacturer") "广州奥松"))
      (libsource (lib "easyedapro") (part "AHT20_C2757850"))
    )
    (comp (ref "LS")
      (value "LTR-303ALS-01")
      (footprint "easyedapro:TDFN-6_L2.0-W2.0-P0.65-BL")
      (fields (field (name "Manufacturer") "LITEON(光宝)"))
      (libsource (lib "easyedapro") (part "LTR-303ALS-01"))
    )
    (comp (ref "R14")
      (value "10kΩ")
      (footprint "easyedapro:R0201")
      (fields
        (field (name "Manufacturer Part") "0201WMF1002TEE")
        (field (name "Manufacturer") "UNI-ROYAL(厚声)")
      )
      (libsource (lib "easyedapro") (part "0201WMF1002TEE"))
    )
    (comp (ref "R43")
      (value "10kΩ")
      (footprint "easyedapro:R0201")
      (fields
        (field (name "Manufacturer Part") "0201WMF1002TEE")
        (field (name "Manufacturer") "UNI-ROYAL(厚声)")
      )
      (libsource (lib "easyedapro") (part "0201WMF1002TEE"))
    )
    (comp (ref "U5")
      (value "SC7A20HTR")
      (footprint "easyedapro:LGA-12_L2.0-W2.0-P0.50-TL")
      (fields (field (name "Manufacturer") "SILAN(士兰微)"))
      (libsource (lib "easyedapro") (part "SC7A20HTR"))
    )
    (comp (ref "U8")
      (value "SLS32AIA020X2USON10")
      (footprint "easyedapro:USON-10_L3.0-W3.0-P0.50-BL-EP")
      (fields (field (name "Manufacturer") "Infineon(英飞凌)"))
      (libsource (lib "easyedapro") (part "SLS32AIA020X2USON10XTMA4"))
    )
    (comp (ref "U9")
      (value "XL9535QF24")
      (footprint "easyedapro:QFN-24_L4.0-W4.0-P0.50-BL-EP2.6")
      (fields (field (name "Manufacturer") "XINLUDA(信路达)"))
      (libsource (lib "easyedapro") (part "XL9535QF24"))
    )
    (comp (ref "U18")
      (value "SE050C2HQ1/Z01SDZ")
      (footprint "easyedapro:WQFN-20_L3.0-W3.0-P0.40-BL-EP1.7")
      (fields (field (name "Manufacturer") "NXP(恩智浦)"))
      (libsource (lib "easyedapro") (part "SE050C2HQ1/Z01SDZ"))
    )
    (comp (ref "C25")
      (value "100nF")
      (footprint "easyedapro:C0201")
      (description "Capacitance:100nF Tolerance:±10% Tolerance:±10% Voltage Rating:10V Temperature Coefficient:X5R")
      (fields
        (field (name "Manufacturer Part") "CL03A104KP3NNNC")
        (field (name "Manufacturer") "SAMSUNG(三星)")
      )
      (libsource (lib "easyedapro") (part "CL03A104KP3NNNC"))
    )
    (comp (ref "C46")
      (value "2.2uF")
      (footprint "easyedapro:C0201")
      (description "Capacitance:2.2uF Tolerance:±20% Tolerance:±20% Voltage Rating:6.3V Temperature Coefficient:X5R")
      (fields
        (field (name "Manufacturer Part") "GRM033R60J225ME47D")
        (field (name "Manufacturer") "muRata(村田)")
      )
      (libsource (lib "easyedapro") (part "GRM033R60J225ME47D"))
    )
    (comp (ref "C47")
      (value "2.2uF")
      (footprint "easyedapro:C0201")
      (description "Capacitance:2.2uF Tolerance:±20% Tolerance:±20% Voltage Rating:6.3V Temperature Coefficient:X5R")
      (fields
        (field (name "Manufacturer Part") "GRM033R60J225ME47D")
        (field (name "Manufacturer") "muRata(村田)")
      )
      (libsource (lib "easyedapro") (part "GRM033R60J225ME47D"))
    )
    (comp (ref "C48")
      (value "2.2uF")
      (footprint "easyedapro:C0201")
      (description "Capacitance:2.2uF Tolerance:±20% Tolerance:±20% Voltage Rating:6.3V Temperature Coefficient:X5R")
      (fields
        (field (name "Manufacturer Part") "GRM033R60J225ME47D")
        (field (name "Manufacturer") "muRata(村田)")
      )
      (libsource (lib "easyedapro") (part "GRM033R60J225ME47D"))
    )
    (comp (ref "C50")
      (value "2.2uF")
      (footprint "easyedapro:C0201")
      (description "Capacitance:2.2uF Tolerance:±20% Tolerance:±20% Voltage Rating:6.3V Temperature Coefficient:X5R")
      (fields
        (field (name "Manufacturer Part") "GRM033R60J225ME47D")
        (field (name "Manufacturer") "muRata(村田)")
      )
      (libsource (lib "easyedapro") (part "GRM033R60J225ME47D"))
    )
    (comp (ref "C65")
      (value "100nF")
      (footprint "easyedapro:C0201")
      (description "Capacitance:100nF Tolerance:±10% Tolerance:±10% Voltage Rating:10V Temperature Coefficient:X5R")
      (fields
        (field (name "Manufacturer Part") "CL03A104KP3NNNC")
        (field (name "Manufacturer") "SAMSUNG(三星)")
      )
      (libsource (lib "easyedapro") (part "CL03A104KP3NNNC"))
    )
    (comp (ref "FPC1")
      (value "FPC-0.5FX-18PWBH15")
      (footprint "easyedapro:FPC-SMD_18P-P0.50_XUNPU_FPC-0.5FX-18PWBH15")
      (fields (field (name "Manufacturer") "XUNPU(讯普)"))
      (libsource (lib "easyedapro") (part "FPC-0.5FX-18PWBH15"))
    )
    (comp (ref "FPC2")
      (value "FPC06-T1T1-2021-A")
      (footprint "easyedapro:FPC-SMD_FPC06-T1T1-2021-A")
      (fields (field (name "Manufacturer") "SHETIME(高钺达)"))
      (libsource (lib "easyedapro") (part "FPC06-T1T1-2021-A"))
    )
    (comp (ref "FPC3")
      (value "FPC-0.5FX-24PH20")
      (footprint "easyedapro:FPC-SMD_24P-P0.50_YUANDI_FPC-0.5FX-24PH20")
      (fields (field (name "Manufacturer") "Yuandi(元迪)"))
      (libsource (lib "easyedapro") (part "FPC-0.5FX-24PH20"))
    )
    (comp (ref "Q4")
      (value "MMBT3904")
      (footprint "easyedapro:SOT-23-3_L2.9-W1.3-P1.90-LS2.4-BR")
      (fields (field (name "Manufacturer") "DOWO(东沃)"))
      (libsource (lib "easyedapro") (part "MMBT3904_C22374713"))
    )
    (comp (ref "R17")
      (value "4.7Ω")
      (fields
        (field (name "Manufacturer Part") "0603WAF470KT5E")
        (field (name "Manufacturer") "UNI-ROYAL(厚声)")
      )
      (libsource (lib "easyedapro") (part "0603WAF470KT5E"))
    )
    (comp (ref "R18")
      (value "10kΩ")
      (footprint "easyedapro:R0201")
      (fields
        (field (name "Manufacturer Part") "0201WMF1002TEE")
        (field (name "Manufacturer") "UNI-ROYAL(厚声)")
      )
      (libsource (lib "easyedapro") (part "0201WMF1002TEE"))
    )
    (comp (ref "R19")
      (value "2kΩ")
      (footprint "easyedapro:R0201")
      (fields
        (field (name "Manufacturer Part") "0201WMF2001TEE")
        (field (name "Manufacturer") "UNI-ROYAL(厚声)")
      )
      (libsource (lib "easyedapro") (part "0201WMF2001TEE"))
    )
    (comp (ref "R20")
      (value "10kΩ")
      (footprint "easyedapro:R0201")
      (fields
        (field (name "Manufacturer Part") "0201WMF1002TEE")
        (field (name "Manufacturer") "UNI-ROYAL(厚声)")
      )
      (libsource (lib "easyedapro") (part "0201WMF1002TEE"))
    )
    (comp (ref "R32")
      (value "0Ω")
      (footprint "easyedapro:R0603")
      (fields
        (field (name "Manufacturer Part") "0603WAF0000T5E")
        (field (name "Manufacturer") "UNI-ROYAL(厚声)")
      )
      (libsource (lib "easyedapro") (part "0603WAF0000T5E"))
    )
    (comp (ref "R33")
      (value "10kΩ")
      (footprint "easyedapro:R0201")
      (fields
        (field (name "Manufacturer Part") "0201WMF1002TEE")
        (field (name "Manufacturer") "UNI-ROYAL(厚声)")
      )
      (libsource (lib "easyedapro") (part "0201WMF1002TEE"))
    )
    (comp (ref "R34")
      (value "10kΩ")
      (footprint "easyedapro:R0201")
      (fields
        (field (name "Manufacturer Part") "0201WMF1002TEE")
        (field (name "Manufacturer") "UNI-ROYAL(厚声)")
      )
      (libsource (lib "easyedapro") (part "0201WMF1002TEE"))
    )
    (comp (ref "U10")
      (value "TSC2007IPWR")
      (footprint "easyedapro:TSSOP-16_L5.0-W4.4-P0.65-LS6.4-BL")
      (fields (field (name "Manufacturer") "TI(德州仪器)"))
      (libsource (lib "easyedapro") (part "TSC2007IPWR"))
    )
    (comp (ref "U11")
      (value "BL8555-28PRA")
      (footprint "easyedapro:SOT-23-5_L3.0-W1.7-P0.95-LS2.8-BL")
      (fields (field (name "Manufacturer") "BL(上海贝岭)"))
      (libsource (lib "easyedapro") (part "BL8555-28PRA"))
    )
    (comp (ref "U12")
      (value "AP7343Q-18W5-7")
      (footprint "easyedapro:SOT-23-5_L3.0-W1.7-P0.95-LS2.8-BR")
      (fields (field (name "Manufacturer") "DIODES(美台)"))
      (libsource (lib "easyedapro") (part "AP7343Q-18W5-7_C3746471"))
    )
    (comp (ref "BOOT")
      (value "B3U-1000P")
      (footprint "easyedapro:KEY-SMD_B3U-1000PM")
      (fields (field (name "Manufacturer") "OMRON(欧姆龙)"))
      (libsource (lib "easyedapro") (part "B3U-1000P"))
    )
    (comp (ref "C3")
      (value "1uF")
      (footprint "easyedapro:C0201")
      (description "Capacitance:1uF Tolerance:±20% Tolerance:±20% Voltage Rating:6.3V Temperature Coefficient:X5R")
      (fields
        (field (name "Manufacturer Part") "CL03A105MQ3CSNH")
        (field (name "Manufacturer") "SAMSUNG(三星)")
      )
      (libsource (lib "easyedapro") (part "CL03A105MQ3CSNH"))
    )
    (comp (ref "C20")
      (value "100nF")
      (footprint "easyedapro:C0201")
      (description "Capacitance:100nF Tolerance:±10% Tolerance:±10% Voltage Rating:10V Temperature Coefficient:X5R")
      (fields
        (field (name "Manufacturer Part") "CL03A104KP3NNNC")
        (field (name "Manufacturer") "SAMSUNG(三星)")
      )
      (libsource (lib "easyedapro") (part "CL03A104KP3NNNC"))
    )
    (comp (ref "C21")
      (value "100nF")
      (footprint "easyedapro:C0201")
      (description "Capacitance:100nF Tolerance:±10% Tolerance:±10% Voltage Rating:10V Temperature Coefficient:X5R")
      (fields
        (field (name "Manufacturer Part") "CL03A104KP3NNNC")
        (field (name "Manufacturer") "SAMSUNG(三星)")
      )
      (libsource (lib "easyedapro") (part "CL03A104KP3NNNC"))
    )
    (comp (ref "C22")
      (value "100nF")
      (footprint "easyedapro:C0201")
      (description "Capacitance:100nF Tolerance:±10% Tolerance:±10% Voltage Rating:10V Temperature Coefficient:X5R")
      (fields
        (field (name "Manufacturer Part") "CL03A104KP3NNNC")
        (field (name "Manufacturer") "SAMSUNG(三星)")
      )
      (libsource (lib "easyedapro") (part "CL03A104KP3NNNC"))
    )
    (comp (ref "C23")
      (value "100nF")
      (footprint "easyedapro:C0201")
      (description "Capacitance:100nF Tolerance:±10% Tolerance:±10% Voltage Rating:10V Temperature Coefficient:X5R")
      (fields
        (field (name "Manufacturer Part") "CL03A104KP3NNNC")
        (field (name "Manufacturer") "SAMSUNG(三星)")
      )
      (libsource (lib "easyedapro") (part "CL03A104KP3NNNC"))
    )
    (comp (ref "C24")
      (value "100nF")
      (footprint "easyedapro:C0201")
      (description "Capacitance:100nF Tolerance:±10% Tolerance:±10% Voltage Rating:10V Temperature Coefficient:X5R")
      (fields
        (field (name "Manufacturer Part") "CL03A104KP3NNNC")
        (field (name "Manufacturer") "SAMSUNG(三星)")
      )
      (libsource (lib "easyedapro") (part "CL03A104KP3NNNC"))
    )
    (comp (ref "IND")
      (value "KT-0603YG")
      (footprint "easyedapro:LED0603-RD")
      (fields (field (name "Manufacturer") "KENTO"))
      (libsource (lib "easyedapro") (part "XL-0603QYGC"))
    )
    (comp (ref "PB1")
      (value "TS24CA")
      (footprint "easyedapro:SW-SMD_2P-TS24CA")
      (fields (field (name "Manufacturer") "SHOU HAN(首韩)"))
      (libsource (lib "easyedapro") (part "TS24CA"))
    )
    (comp (ref "PB2")
      (value "TS24CA")
      (footprint "easyedapro:SW-SMD_2P-TS24CA")
      (fields (field (name "Manufacturer") "SHOU HAN(首韩)"))
      (libsource (lib "easyedapro") (part "TS24CA"))
    )
    (comp (ref "PWR")
      (value "KT-0603R")
      (fields (field (name "Manufacturer") "KENTO"))
      (libsource (lib "easyedapro") (part "KT-0603R"))
    )
    (comp (ref "R1")
      (value "10kΩ")
      (footprint "easyedapro:R0201")
      (fields
        (field (name "Manufacturer Part") "0201WMF1002TEE")
        (field (name "Manufacturer") "UNI-ROYAL(厚声)")
      )
      (libsource (lib "easyedapro") (part "0201WMF1002TEE"))
    )
    (comp (ref "R4")
      (value "10kΩ")
      (footprint "easyedapro:R0201")
      (fields
        (field (name "Manufacturer Part") "0201WMF1002TEE")
        (field (name "Manufacturer") "UNI-ROYAL(厚声)")
      )
      (libsource (lib "easyedapro") (part "0201WMF1002TEE"))
    )
    (comp (ref "R6")
      (value "10kΩ")
      (footprint "easyedapro:R0201")
      (fields
        (field (name "Manufacturer Part") "0201WMF1002TEE")
        (field (name "Manufacturer") "UNI-ROYAL(厚声)")
      )
      (libsource (lib "easyedapro") (part "0201WMF1002TEE"))
    )
    (comp (ref "R7")
      (value "10kΩ")
      (footprint "easyedapro:R0201")
      (fields
        (field (name "Manufacturer Part") "0201WMF1002TEE")
        (field (name "Manufacturer") "UNI-ROYAL(厚声)")
      )
      (libsource (lib "easyedapro") (part "0201WMF1002TEE"))
    )
    (comp (ref "R15")
      (value "2kΩ")
      (footprint "easyedapro:R0201")
      (fields
        (field (name "Manufacturer Part") "0201WMF2001TEE")
        (field (name "Manufacturer") "UNI-ROYAL(厚声)")
      )
      (libsource (lib "easyedapro") (part "0201WMF2001TEE"))
    )
    (comp (ref "R16")
      (value "330Ω")
      (footprint "easyedapro:R0201")
      (fields
        (field (name "Manufacturer Part") "0201WMJ0331TEE")
        (field (name "Manufacturer") "UNI-ROYAL(厚声)")
      )
      (libsource (lib "easyedapro") (part "0201WMF2001TEE"))
    )
    (comp (ref "R37")
      (value "10kΩ")
      (footprint "easyedapro:R0201")
      (fields
        (field (name "Manufacturer Part") "0201WMF1002TEE")
        (field (name "Manufacturer") "UNI-ROYAL(厚声)")
      )
      (libsource (lib "easyedapro") (part "0201WMF1002TEE"))
    )
    (comp (ref "R38")
      (value "10kΩ")
      (footprint "easyedapro:R0201")
      (fields
        (field (name "Manufacturer Part") "0201WMF1002TEE")
        (field (name "Manufacturer") "UNI-ROYAL(厚声)")
      )
      (libsource (lib "easyedapro") (part "0201WMF1002TEE"))
    )
    (comp (ref "R39")
      (value "10kΩ")
      (footprint "easyedapro:R0201")
      (fields
        (field (name "Manufacturer Part") "0201WMF1002TEE")
        (field (name "Manufacturer") "UNI-ROYAL(厚声)")
      )
      (libsource (lib "easyedapro") (part "0201WMF1002TEE"))
    )
    (comp (ref "RGB1")
      (value "XL-0807RGBC-2812B")
      (footprint "easyedapro:LED-SMD_4P-L2.0-W1.8_XL-0807RGBC-WS2812B")
      (fields (field (name "Manufacturer") "XINGLIGHT(成兴光)"))
      (libsource (lib "easyedapro") (part "XL-0807RGBC-WS2812B"))
    )
    (comp (ref "RGB2")
      (value "XL-0807RGBC-2812B")
      (footprint "easyedapro:LED-SMD_4P-L2.0-W1.8_XL-0807RGBC-WS2812B")
      (fields (field (name "Manufacturer") "XINGLIGHT(成兴光)"))
      (libsource (lib "easyedapro") (part "XL-0807RGBC-WS2812B"))
    )
    (comp (ref "RST")
      (value "B3U-1000P")
      (footprint "easyedapro:KEY-SMD_B3U-1000PM")
      (fields (field (name "Manufacturer") "OMRON(欧姆龙)"))
      (libsource (lib "easyedapro") (part "B3U-1000P"))
    )
    (comp (ref "SW1")
      (value "SKPMAPE010")
      (footprint "easyedapro:KEY-SMD_2P-L6.0-W6.0-P6.00")
      (fields (field (name "Manufacturer") "ALPSALPINE(阿尔卑斯阿尔派)"))
      (libsource (lib "easyedapro") (part "SKPMAPE010"))
    )
    (comp (ref "SW2")
      (value "SKPMAPE010")
      (footprint "easyedapro:KEY-SMD_2P-L6.0-W6.0-P6.00")
      (fields (field (name "Manufacturer") "ALPSALPINE(阿尔卑斯阿尔派)"))
      (libsource (lib "easyedapro") (part "SKPMAPE010"))
    )
    (comp (ref "SW3")
      (value "SKPMAPE010")
      (footprint "easyedapro:KEY-SMD_2P-L6.0-W6.0-P6.00")
      (fields (field (name "Manufacturer") "ALPSALPINE(阿尔卑斯阿尔派)"))
      (libsource (lib "easyedapro") (part "SKPMAPE010"))
    )
    (comp (ref "SW4")
      (value "EVQQ2B03W")
      (footprint "easyedapro:KEY-SMD_4P-L6.5-W6.0-P4.0-LS6.6")
      (fields (field (name "Manufacturer") "PANASONIC(松下)"))
      (libsource (lib "easyedapro") (part "EVQQ2B03W"))
    )
    (comp (ref "SW5")
      (value "EVQQ2B03W")
      (footprint "easyedapro:KEY-SMD_4P-L6.5-W6.0-P4.0-LS6.6")
      (fields (field (name "Manufacturer") "PANASONIC(松下)"))
      (libsource (lib "easyedapro") (part "EVQQ2B03W"))
    )
    (comp (ref "SW6")
      (value "EVQQ2B03W")
      (footprint "easyedapro:KEY-SMD_4P-L6.5-W6.0-P4.0-LS6.6")
      (fields (field (name "Manufacturer") "PANASONIC(松下)"))
      (libsource (lib "easyedapro") (part "EVQQ2B03W"))
    )
    (comp (ref "C2")
      (value "22uF")
      (description "Capacitance:22uF Tolerance:±20% Tolerance:±20% Voltage Rating:6.3V Temperature Coefficient:X5R")
      (fields
        (field (name "Manufacturer Part") "CL05A226MQ5QUNC")
        (field (name "Manufacturer") "SAMSUNG(三星)")
      )
      (libsource (lib "easyedapro") (part "CL05A226MQ5QUNC"))
    )
    (comp (ref "C6")
      (value "15pF")
      (footprint "easyedapro:C0201")
      (description "Capacitance:15pF Tolerance:±5% Tolerance:±5% Voltage Rating:50V Temperature Coefficient:C0G")
      (fields
        (field (name "Manufacturer Part") "GRM0335C1H150JA01D")
        (field (name "Manufacturer") "muRata(村田)")
      )
      (libsource (lib "easyedapro") (part "GRM0335C1H150JA01D"))
    )
    (comp (ref "C18")
      (value "100nF")
      (footprint "easyedapro:C0201")
      (description "Capacitance:100nF Tolerance:±10% Tolerance:±10% Voltage Rating:10V Temperature Coefficient:X5R")
      (fields
        (field (name "Manufacturer Part") "CL03A104KP3NNNC")
        (field (name "Manufacturer") "SAMSUNG(三星)")
      )
      (libsource (lib "easyedapro") (part "CL03A104KP3NNNC"))
    )
    (comp (ref "C26")
      (value "1uF")
      (footprint "easyedapro:C0201")
      (description "Capacitance:1uF Tolerance:±20% Tolerance:±20% Voltage Rating:6.3V Temperature Coefficient:X5R")
      (fields
        (field (name "Manufacturer Part") "CL03A105MQ3CSNH")
        (field (name "Manufacturer") "SAMSUNG(三星)")
      )
      (libsource (lib "easyedapro") (part "CL03A105MQ3CSNH"))
    )
    (comp (ref "C27")
      (value "1uF")
      (footprint "easyedapro:C0201")
      (description "Capacitance:1uF Tolerance:±20% Tolerance:±20% Voltage Rating:6.3V Temperature Coefficient:X5R")
      (fields
        (field (name "Manufacturer Part") "CL03A105MQ3CSNH")
        (field (name "Manufacturer") "SAMSUNG(三星)")
      )
      (libsource (lib "easyedapro") (part "CL03A105MQ3CSNH"))
    )
    (comp (ref "C28")
      (value "1uF")
      (footprint "easyedapro:C0201")
      (description "Capacitance:1uF Tolerance:±20% Tolerance:±20% Voltage Rating:6.3V Temperature Coefficient:X5R")
      (fields
        (field (name "Manufacturer Part") "CL03A105MQ3CSNH")
        (field (name "Manufacturer") "SAMSUNG(三星)")
      )
      (libsource (lib "easyedapro") (part "CL03A105MQ3CSNH"))
    )
    (comp (ref "C29")
      (value "100nF")
      (footprint "easyedapro:C0201")
      (description "Capacitance:100nF Tolerance:±10% Tolerance:±10% Voltage Rating:10V Temperature Coefficient:X5R")
      (fields
        (field (name "Manufacturer Part") "CL03A104KP3NNNC")
        (field (name "Manufacturer") "SAMSUNG(三星)")
      )
      (libsource (lib "easyedapro") (part "CL03A104KP3NNNC"))
    )
    (comp (ref "C30")
      (value "100nF")
      (footprint "easyedapro:C0201")
      (description "Capacitance:100nF Tolerance:±10% Tolerance:±10% Voltage Rating:10V Temperature Coefficient:X5R")
      (fields
        (field (name "Manufacturer Part") "CL03A104KP3NNNC")
        (field (name "Manufacturer") "SAMSUNG(三星)")
      )
      (libsource (lib "easyedapro") (part "CL03A104KP3NNNC"))
    )
    (comp (ref "C36")
      (value "100nF")
      (footprint "easyedapro:C0201")
      (description "Capacitance:100nF Tolerance:±10% Tolerance:±10% Voltage Rating:10V Temperature Coefficient:X5R")
      (fields
        (field (name "Manufacturer Part") "CL03A104KP3NNNC")
        (field (name "Manufacturer") "SAMSUNG(三星)")
      )
      (libsource (lib "easyedapro") (part "CL03A104KP3NNNC"))
    )
    (comp (ref "C37")
      (value "1uF")
      (footprint "easyedapro:C0201")
      (description "Capacitance:1uF Tolerance:±20% Tolerance:±20% Voltage Rating:6.3V Temperature Coefficient:X5R")
      (fields
        (field (name "Manufacturer Part") "CL03A105MQ3CSNH")
        (field (name "Manufacturer") "SAMSUNG(三星)")
      )
      (libsource (lib "easyedapro") (part "CL03A105MQ3CSNH"))
    )
    (comp (ref "C38")
      (value "1uF")
      (footprint "easyedapro:C0201")
      (description "Capacitance:1uF Tolerance:±20% Tolerance:±20% Voltage Rating:6.3V Temperature Coefficient:X5R")
      (fields
        (field (name "Manufacturer Part") "CL03A105MQ3CSNH")
        (field (name "Manufacturer") "SAMSUNG(三星)")
      )
      (libsource (lib "easyedapro") (part "CL03A105MQ3CSNH"))
    )
    (comp (ref "C39")
      (value "1uF")
      (footprint "easyedapro:C0201")
      (description "Capacitance:1uF Tolerance:±20% Tolerance:±20% Voltage Rating:6.3V Temperature Coefficient:X5R")
      (fields
        (field (name "Manufacturer Part") "CL03A105MQ3CSNH")
        (field (name "Manufacturer") "SAMSUNG(三星)")
      )
      (libsource (lib "easyedapro") (part "CL03A105MQ3CSNH"))
    )
    (comp (ref "C40")
      (value "15pF")
      (footprint "easyedapro:C0201")
      (description "Capacitance:15pF Tolerance:±5% Tolerance:±5% Voltage Rating:50V Temperature Coefficient:C0G")
      (fields
        (field (name "Manufacturer Part") "GRM0335C1H150JA01D")
        (field (name "Manufacturer") "muRata(村田)")
      )
      (libsource (lib "easyedapro") (part "GRM0335C1H150JA01D"))
    )
    (comp (ref "C41")
      (value "100nF")
      (footprint "easyedapro:C0201")
      (description "Capacitance:100nF Tolerance:±10% Tolerance:±10% Voltage Rating:10V Temperature Coefficient:X5R")
      (fields
        (field (name "Manufacturer Part") "CL03A104KP3NNNC")
        (field (name "Manufacturer") "SAMSUNG(三星)")
      )
      (libsource (lib "easyedapro") (part "CL03A104KP3NNNC"))
    )
    (comp (ref "C42")
      (value "1uF")
      (footprint "easyedapro:C0201")
      (description "Capacitance:1uF Tolerance:±20% Tolerance:±20% Voltage Rating:6.3V Temperature Coefficient:X5R")
      (fields
        (field (name "Manufacturer Part") "CL03A105MQ3CSNH")
        (field (name "Manufacturer") "SAMSUNG(三星)")
      )
      (libsource (lib "easyedapro") (part "CL03A105MQ3CSNH"))
    )
    (comp (ref "C43")
      (value "1uF")
      (footprint "easyedapro:C0201")
      (description "Capacitance:1uF Tolerance:±20% Tolerance:±20% Voltage Rating:6.3V Temperature Coefficient:X5R")
      (fields
        (field (name "Manufacturer Part") "CL03A105MQ3CSNH")
        (field (name "Manufacturer") "SAMSUNG(三星)")
      )
      (libsource (lib "easyedapro") (part "CL03A105MQ3CSNH"))
    )
    (comp (ref "C45")
      (value "22uF")
      (description "Capacitance:22uF Tolerance:±20% Tolerance:±20% Voltage Rating:6.3V Temperature Coefficient:X5R")
      (fields
        (field (name "Manufacturer Part") "CL05A226MQ5QUNC")
        (field (name "Manufacturer") "SAMSUNG(三星)")
      )
      (libsource (lib "easyedapro") (part "CL05A226MQ5QUNC"))
    )
    (comp (ref "C68")
      (value "10uF")
      (description "Capacitance:10uF Tolerance:±20% Tolerance:±20% Voltage Rating:6.3V Temperature Coefficient:X5R")
      (fields
        (field (name "Manufacturer Part") "CL05A106MQ5NUNC")
        (field (name "Manufacturer") "SAMSUNG(三星)")
      )
      (libsource (lib "easyedapro") (part "CL05A106MQ5NUNC"))
    )
    (comp (ref "MIC1")
      (value "MSM381ACP003")
      (footprint "easyedapro:MIC-SMD_4P-L2.8-W1.9-TR_MSM381ACP003")
      (fields (field (name "Manufacturer") "MEMS(敏芯微)"))
      (libsource (lib "easyedapro") (part "MSM381ACP003_C51928212"))
    )
    (comp (ref "MIC2")
      (value "MSM381ACP003")
      (footprint "easyedapro:MIC-SMD_4P-L2.8-W1.9-TR_MSM381ACP003")
      (fields (field (name "Manufacturer") "MEMS(敏芯微)"))
      (libsource (lib "easyedapro") (part "MSM381ACP003_C51928212"))
    )
    (comp (ref "R21")
      (value "3.3kΩ")
      (footprint "easyedapro:R0201")
      (fields
        (field (name "Manufacturer Part") "0201WMF3301TEE")
        (field (name "Manufacturer") "UNI-ROYAL(厚声)")
      )
      (libsource (lib "easyedapro") (part "0201WMF3301TEE"))
    )
    (comp (ref "R22")
      (value "0Ω")
      (footprint "easyedapro:R0603")
      (fields
        (field (name "Manufacturer Part") "0603WAF0000T5E")
        (field (name "Manufacturer") "UNI-ROYAL(厚声)")
      )
      (libsource (lib "easyedapro") (part "0603WAF0000T5E"))
    )
    (comp (ref "R35")
      (value "10kΩ")
      (footprint "easyedapro:R0201")
      (fields
        (field (name "Manufacturer Part") "0201WMF1002TEE")
        (field (name "Manufacturer") "UNI-ROYAL(厚声)")
      )
      (libsource (lib "easyedapro") (part "0201WMF1002TEE"))
    )
    (comp (ref "R36")
      (value "10kΩ")
      (footprint "easyedapro:R0201")
      (fields
        (field (name "Manufacturer Part") "0201WMF1002TEE")
        (field (name "Manufacturer") "UNI-ROYAL(厚声)")
      )
      (libsource (lib "easyedapro") (part "0201WMF1002TEE"))
    )
    (comp (ref "R44")
      (value "10kΩ")
      (footprint "easyedapro:R0201")
      (fields
        (field (name "Manufacturer Part") "0201WMF1002TEE")
        (field (name "Manufacturer") "UNI-ROYAL(厚声)")
      )
      (libsource (lib "easyedapro") (part "0201WMF1002TEE"))
    )
    (comp (ref "SP1")
      (value "SM02B-SRSS-TB(LF)(SN)")
      (footprint "easyedapro:CONN-SMD_2P-P1.00_SM02B-SRSS-TB-LF-SN")
      (fields (field (name "Manufacturer") "JST"))
      (libsource (lib "easyedapro") (part "SM02B-SRSS-TB (LF)(SN)"))
    )
    (comp (ref "U13")
      (value "NS4168")
      (footprint "easyedapro:ESOP-8_L4.9-W3.9-P1.27-LS6.0-BL-EP")
      (description "Class:Class D Output Power:2.5Wx1@4Ω Voltage - Supply:3V~5.5V Voltage - Supply:3V~5.5V")
      (fields (field (name "Manufacturer") "Nsiway(纳芯威)"))
      (libsource (lib "easyedapro") (part "NS4168_C910588"))
    )
    (comp (ref "U14")
      (value "ES7243E")
      (footprint "easyedapro:QFN-20_L3.0-W3.0-P0.40-BL-EP1.7")
      (fields (field (name "Manufacturer") "Everest-semi(顺芯)"))
      (libsource (lib "easyedapro") (part "ES7243E"))
    )
  )
  (nets
    (net (code "1") (name "1V8") (class "Default")
      (node (ref "C50") (pin "2") (pinfunction "2_2") (pintype "input"))
      (node (ref "FPC3") (pin "15") (pinfunction "15_15") (pintype "unspecified"))
      (node (ref "U12") (pin "5") (pinfunction "VOUT_5") (pintype "unspecified"))
    )
    (net (code "2") (name "2V8") (class "Default")
      (node (ref "C47") (pin "2") (pinfunction "2_2") (pintype "input"))
      (node (ref "FPC3") (pin "14") (pinfunction "14_14") (pintype "unspecified"))
      (node (ref "FPC3") (pin "21") (pinfunction "21_21") (pintype "unspecified"))
      (node (ref "U11") (pin "5") (pinfunction "VOUT_5") (pintype "unspecified"))
    )
    (net (code "3") (name "3V3") (class "Default")
      (node (ref "C1") (pin "2") (pinfunction "2_2") (pintype "input"))
      (node (ref "C12") (pin "2") (pinfunction "2_2") (pintype "unspecified"))
      (node (ref "C18") (pin "2") (pinfunction "2_2") (pintype "unspecified"))
      (node (ref "C19") (pin "2") (pinfunction "2_2") (pintype "unspecified"))
      (node (ref "C2") (pin "2") (pinfunction "2_2") (pintype "unspecified"))
      (node (ref "C22") (pin "2") (pinfunction "2_2") (pintype "unspecified"))
      (node (ref "C23") (pin "2") (pinfunction "2_2") (pintype "unspecified"))
      (node (ref "C24") (pin "2") (pinfunction "2_2") (pintype "unspecified"))
      (node (ref "C26") (pin "2") (pinfunction "2_2") (pintype "input"))
      (node (ref "C29") (pin "2") (pinfunction "2_2") (pintype "unspecified"))
      (node (ref "C30") (pin "2") (pinfunction "2_2") (pintype "unspecified"))
      (node (ref "C36") (pin "2") (pinfunction "2_2") (pintype "unspecified"))
      (node (ref "C37") (pin "2") (pinfunction "2_2") (pintype "input"))
      (node (ref "C41") (pin "2") (pinfunction "2_2") (pintype "unspecified"))
      (node (ref "C45") (pin "2") (pinfunction "2_2") (pintype "unspecified"))
      (node (ref "C46") (pin "2") (pinfunction "2_2") (pintype "input"))
      (node (ref "C48") (pin "2") (pinfunction "2_2") (pintype "input"))
      (node (ref "C59") (pin "2") (pinfunction "2_2") (pintype "unspecified"))
      (node (ref "C60") (pin "2") (pinfunction "2_2") (pintype "unspecified"))
      (node (ref "C61") (pin "2") (pinfunction "2_2") (pintype "unspecified"))
      (node (ref "C62") (pin "2") (pinfunction "2_2") (pintype "unspecified"))
      (node (ref "C63") (pin "2") (pinfunction "2_2") (pintype "unspecified"))
      (node (ref "C64") (pin "2") (pinfunction "2_2") (pintype "unspecified"))
      (node (ref "C65") (pin "2") (pinfunction "2_2") (pintype "unspecified"))
      (node (ref "C_I2C") (pin "1") (pinfunction "1_1") (pintype "unspecified"))
      (node (ref "C_P0") (pin "1") (pinfunction "1_1") (pintype "unspecified"))
      (node (ref "C_P1-3") (pin "1") (pinfunction "1_1") (pintype "unspecified"))
      (node (ref "C_P4-5") (pin "1") (pinfunction "1_1") (pintype "unspecified"))
      (node (ref "FPC1") (pin "10") (pinfunction "10_10") (pintype "unspecified"))
      (node (ref "FPC1") (pin "9") (pinfunction "9_9") (pintype "unspecified"))
      (node (ref "FPC2") (pin "1") (pinfunction "1_1") (pintype "unspecified"))
      (node (ref "HUM") (pin "5") (pinfunction "VDD_5") (pintype "unspecified"))
      (node (ref "LS") (pin "1") (pinfunction "VDD_1") (pintype "unspecified"))
      (node (ref "MIC1") (pin "1") (pinfunction "VDD_1") (pintype "unspecified"))
      (node (ref "MIC2") (pin "1") (pinfunction "VDD_1") (pintype "unspecified"))
      (node (ref "R1") (pin "2") (pinfunction "2_2") (pintype "unspecified"))
      (node (ref "R12") (pin "1") (pinfunction "1_1") (pintype "unspecified"))
      (node (ref "R13") (pin "2") (pinfunction "2_2") (pintype "unspecified"))
      (node (ref "R14") (pin "2") (pinfunction "2_2") (pintype "unspecified"))
      (node (ref "R15") (pin "2") (pinfunction "2_2") (pintype "input"))
      (node (ref "R20") (pin "2") (pinfunction "2_2") (pintype "unspecified"))
      (node (ref "R23") (pin "2") (pinfunction "2_2") (pintype "input"))
      (node (ref "R29") (pin "2") (pinfunction "2_2") (pintype "unspecified"))
      (node (ref "R31") (pin "1") (pinfunction "1_1") (pintype "unspecified"))
      (node (ref "R33") (pin "1") (pinfunction "1_1") (pintype "unspecified"))
      (node (ref "R34") (pin "2") (pinfunction "2_2") (pintype "unspecified"))
      (node (ref "R35") (pin "1") (pinfunction "1_1") (pintype "unspecified"))
      (node (ref "R36") (pin "2") (pinfunction "2_2") (pintype "unspecified"))
      (node (ref "R37") (pin "2") (pinfunction "2_2") (pintype "unspecified"))
      (node (ref "R38") (pin "2") (pinfunction "2_2") (pintype "unspecified"))
      (node (ref "R39") (pin "2") (pinfunction "2_2") (pintype "unspecified"))
      (node (ref "R4") (pin "2") (pinfunction "2_2") (pintype "unspecified"))
      (node (ref "R43") (pin "2") (pinfunction "2_2") (pintype "unspecified"))
      (node (ref "R6") (pin "2") (pinfunction "2_2") (pintype "unspecified"))
      (node (ref "R7") (pin "2") (pinfunction "2_2") (pintype "unspecified"))
      (node (ref "RGB1") (pin "4") (pinfunction "VDD_4") (pintype "unspecified"))
      (node (ref "RGB2") (pin "4") (pinfunction "VDD_4") (pintype "unspecified"))
      (node (ref "TF1") (pin "4") (pinfunction "VDD_4") (pintype "unspecified"))
      (node (ref "U1") (pin "2") (pinfunction "3V3_2") (pintype "unspecified"))
      (node (ref "U10") (pin "1") (pinfunction "VDDREF_1") (pintype "unspecified"))
      (node (ref "U10") (pin "13") (pinfunction "A1_13") (pintype "unspecified"))
      (node (ref "U11") (pin "1") (pinfunction "VDD_1") (pintype "unspecified"))
      (node (ref "U11") (pin "3") (pinfunction "CE_3") (pintype "unspecified"))
      (node (ref "U12") (pin "1") (pinfunction "VIN_1") (pintype "unspecified"))
      (node (ref "U12") (pin "3") (pinfunction "EN_3") (pintype "unspecified"))
      (node (ref "U13") (pin "6") (pinfunction "VDD_6") (pintype "unspecified"))
      (node (ref "U14") (pin "1") (pinfunction "VDDP_1") (pintype "unspecified"))
      (node (ref "U14") (pin "12") (pinfunction "VDDA_12") (pintype "unspecified"))
      (node (ref "U14") (pin "17") (pinfunction "AD0_17") (pintype "unspecified"))
      (node (ref "U14") (pin "5") (pinfunction "VDDD_5") (pintype "unspecified"))
      (node (ref "U18") (pin "12") (pinfunction "VIN_12") (pintype "unspecified"))
      (node (ref "U2") (pin "8") (pinfunction "VCC_8") (pintype "unspecified"))
      (node (ref "U4") (pin "4") (pinfunction "VO_4") (pintype "unspecified"))
      (node (ref "U5") (pin "3") (pinfunction "VDDIO_3") (pintype "unspecified"))
      (node (ref "U5") (pin "7") (pinfunction "VDD_7") (pintype "unspecified"))
      (node (ref "U8") (pin "10") (pinfunction "VCC_10") (pintype "unspecified"))
      (node (ref "U9") (pin "21") (pinfunction "VCC_21") (pintype "unspecified"))
    )
    (net (code "4") (name "AGND") (class "Default")
      (node (ref "C18") (pin "1") (pinfunction "1_1") (pintype "unspecified"))
      (node (ref "C26") (pin "1") (pinfunction "1_1") (pintype "input"))
      (node (ref "C28") (pin "2") (pinfunction "2_2") (pintype "input"))
      (node (ref "C36") (pin "1") (pinfunction "1_1") (pintype "unspecified"))
      (node (ref "C37") (pin "1") (pinfunction "1_1") (pintype "input"))
      (node (ref "C39") (pin "2") (pinfunction "2_2") (pintype "input"))
      (node (ref "C40") (pin "1") (pinfunction "1_1") (pintype "input"))
      (node (ref "C42") (pin "1") (pinfunction "1_1") (pintype "input"))
      (node (ref "C43") (pin "1") (pinfunction "1_1") (pintype "input"))
      (node (ref "C6") (pin "1") (pinfunction "1_1") (pintype "input"))
      (node (ref "MIC1") (pin "3") (pinfunction "GND_3") (pintype "unspecified"))
      (node (ref "MIC1") (pin "4") (pinfunction "GND_4") (pintype "unspecified"))
      (node (ref "MIC2") (pin "3") (pinfunction "GND_3") (pintype "unspecified"))
      (node (ref "MIC2") (pin "4") (pinfunction "GND_4") (pintype "unspecified"))
      (node (ref "R22") (pin "1") (pinfunction "1_1") (pintype "input"))
    )
    (net (code "5") (name "BOOT") (class "Default")
      (node (ref "BOOT") (pin "2") (pinfunction "2_2") (pintype "unspecified"))
      (node (ref "R4") (pin "1") (pinfunction "1_1") (pintype "unspecified"))
      (node (ref "U1") (pin "27") (pinfunction "IO0_27") (pintype "unspecified"))
      (node (ref "U13") (pin "3") (pinfunction "BCLK_3") (pintype "unspecified"))
      (node (ref "U14") (pin "6") (pinfunction "SCLK_6") (pintype "unspecified"))
    )
    (net (code "6") (name "BUS_INT") (class "Default")
      (node (ref "R14") (pin "1") (pinfunction "1_1") (pintype "unspecified"))
      (node (ref "U1") (pin "37") (pinfunction "TXD0_37") (pintype "unspecified"))
      (node (ref "U9") (pin "22") (pinfunction "INT#_22") (pintype "unspecified"))
    )
    (net (code "7") (name "CC1") (class "Default")
      (node (ref "R5") (pin "1") (pinfunction "1_1") (pintype "input"))
      (node (ref "U3") (pin "3") (pinfunction "IO_3") (pintype "input"))
      (node (ref "USB1") (pin "A5") (pinfunction "CC1_A5") (pintype "unspecified"))
    )
    (net (code "8") (name "CC2") (class "Default")
      (node (ref "R3") (pin "2") (pinfunction "2_2") (pintype "input"))
      (node (ref "U3") (pin "1") (pinfunction "IO_1") (pintype "input"))
      (node (ref "USB1") (pin "B5") (pinfunction "CC2_B5") (pintype "unspecified"))
    )
    (net (code "9") (name "CS3") (class "Default")
      (node (ref "R28") (pin "2") (pinfunction "2_2") (pintype "unspecified"))
      (node (ref "TF1") (pin "2") (pinfunction "CD/DAT3_2") (pintype "unspecified"))
      (node (ref "U1") (pin "33") (pinfunction "IO40_33") (pintype "unspecified"))
    )
    (net (code "10") (name "C_D2") (class "Default")
      (node (ref "FPC3") (pin "6") (pinfunction "6_6") (pintype "unspecified"))
      (node (ref "U1") (pin "12") (pinfunction "IO8_12") (pintype "unspecified"))
    )
    (net (code "11") (name "C_D3") (class "Default")
      (node (ref "FPC3") (pin "4") (pinfunction "4_4") (pintype "unspecified"))
      (node (ref "U1") (pin "18") (pinfunction "IO10_18") (pintype "unspecified"))
    )
    (net (code "12") (name "C_D4") (class "Default")
      (node (ref "FPC3") (pin "3") (pinfunction "3_3") (pintype "unspecified"))
      (node (ref "U1") (pin "19") (pinfunction "IO11_19") (pintype "unspecified"))
    )
    (net (code "13") (name "C_D5") (class "Default")
      (node (ref "FPC3") (pin "5") (pinfunction "5_5") (pintype "unspecified"))
      (node (ref "U1") (pin "17") (pinfunction "IO9_17") (pintype "unspecified"))
    )
    (net (code "14") (name "C_D6") (class "Default")
      (node (ref "FPC3") (pin "7") (pinfunction "7_7") (pintype "unspecified"))
      (node (ref "U1") (pin "11") (pinfunction "IO18_11") (pintype "unspecified"))
    )
    (net (code "15") (name "C_D7") (class "Default")
      (node (ref "FPC3") (pin "9") (pinfunction "9_9") (pintype "unspecified"))
      (node (ref "U1") (pin "9") (pinfunction "IO16_9") (pintype "unspecified"))
    )
    (net (code "16") (name "C_D8") (class "Default")
      (node (ref "FPC3") (pin "11") (pinfunction "11_11") (pintype "unspecified"))
      (node (ref "U1") (pin "8") (pinfunction "IO15_8") (pintype "unspecified"))
    )
    (net (code "17") (name "C_D9") (class "Default")
      (node (ref "FPC3") (pin "13") (pinfunction "13_13") (pintype "unspecified"))
      (node (ref "U1") (pin "6") (pinfunction "IO6_6") (pintype "unspecified"))
    )
    (net (code "18") (name "C_HREF") (class "Default")
      (node (ref "FPC3") (pin "16") (pinfunction "16_16") (pintype "unspecified"))
      (node (ref "U1") (pin "5") (pinfunction "IO5_5") (pintype "unspecified"))
    )
    (net (code "19") (name "C_PCLK") (class "Default")
      (node (ref "FPC3") (pin "8") (pinfunction "8_8") (pintype "unspecified"))
      (node (ref "U1") (pin "10") (pinfunction "IO17_10") (pintype "unspecified"))
    )
    (net (code "20") (name "C_RST") (class "Default")
      (node (ref "FPC3") (pin "19") (pinfunction "19_19") (pintype "unspecified"))
      (node (ref "U9") (pin "3") (pinfunction "P02_3") (pintype "unspecified"))
    )
    (net (code "21") (name "C_VSYC") (class "Default")
      (node (ref "FPC3") (pin "18") (pinfunction "18_18") (pintype "unspecified"))
      (node (ref "U1") (pin "4") (pinfunction "IO4_4") (pintype "unspecified"))
    )
    (net (code "22") (name "C_XCLK") (class "Default")
      (node (ref "FPC3") (pin "12") (pinfunction "12_12") (pintype "unspecified"))
      (node (ref "U1") (pin "7") (pinfunction "IO7_7") (pintype "unspecified"))
    )
    (net (code "23") (name "DN") (class "Default")
      (node (ref "U1") (pin "13") (pinfunction "IO19_13") (pintype "unspecified"))
      (node (ref "U3") (pin "4") (pinfunction "IO_4") (pintype "input"))
      (node (ref "USB1") (pin "A7") (pinfunction "DN1_A7") (pintype "unspecified"))
      (node (ref "USB1") (pin "B7") (pinfunction "DN2_B7") (pintype "unspecified"))
    )
    (net (code "24") (name "DP") (class "Default")
      (node (ref "U1") (pin "14") (pinfunction "IO20_14") (pintype "unspecified"))
      (node (ref "U3") (pin "6") (pinfunction "IO_6") (pintype "input"))
      (node (ref "USB1") (pin "A6") (pinfunction "DP1_A6") (pintype "unspecified"))
      (node (ref "USB1") (pin "B6") (pinfunction "DP2_B6") (pintype "unspecified"))
    )
    (net (code "25") (name "GND") (class "Default")
      (node (ref "BAT1") (pin "1") (pinfunction "1_1") (pintype "unspecified"))
      (node (ref "BAT1") (pin "3") (pinfunction "3_3") (pintype "unspecified"))
      (node (ref "BAT1") (pin "4") (pinfunction "4_4") (pintype "unspecified"))
      (node (ref "BOOT") (pin "1") (pinfunction "1_1") (pintype "unspecified"))
      (node (ref "C1") (pin "1") (pinfunction "1_1") (pintype "input"))
      (node (ref "C12") (pin "1") (pinfunction "1_1") (pintype "unspecified"))
      (node (ref "C19") (pin "1") (pinfunction "1_1") (pintype "unspecified"))
      (node (ref "C2") (pin "1") (pinfunction "1_1") (pintype "unspecified"))
      (node (ref "C20") (pin "1") (pinfunction "1_1") (pintype "unspecified"))
      (node (ref "C21") (pin "1") (pinfunction "1_1") (pintype "unspecified"))
      (node (ref "C22") (pin "1") (pinfunction "1_1") (pintype "unspecified"))
      (node (ref "C23") (pin "1") (pinfunction "1_1") (pintype "unspecified"))
      (node (ref "C24") (pin "1") (pinfunction "1_1") (pintype "unspecified"))
      (node (ref "C25") (pin "1") (pinfunction "1_1") (pintype "unspecified"))
      (node (ref "C29") (pin "1") (pinfunction "1_1") (pintype "unspecified"))
      (node (ref "C3") (pin "1") (pinfunction "1_1") (pintype "input"))
      (node (ref "C30") (pin "1") (pinfunction "1_1") (pintype "unspecified"))
      (node (ref "C41") (pin "1") (pinfunction "1_1") (pintype "unspecified"))
      (node (ref "C45") (pin "1") (pinfunction "1_1") (pintype "unspecified"))
      (node (ref "C46") (pin "1") (pinfunction "1_1") (pintype "input"))
      (node (ref "C47") (pin "1") (pinfunction "1_1") (pintype "input"))
      (node (ref "C48") (pin "1") (pinfunction "1_1") (pintype "input"))
      (node (ref "C50") (pin "1") (pinfunction "1_1") (pintype "input"))
      (node (ref "C51") (pin "1") (pinfunction "1_1") (pintype "unspecified"))
      (node (ref "C52") (pin "1") (pinfunction "1_1") (pintype "unspecified"))
      (node (ref "C54") (pin "2") (pinfunction "2_2") (pintype "unspecified"))
      (node (ref "C58") (pin "1") (pinfunction "1_1") (pintype "unspecified"))
      (node (ref "C59") (pin "1") (pinfunction "1_1") (pintype "unspecified"))
      (node (ref "C60") (pin "1") (pinfunction "1_1") (pintype "unspecified"))
      (node (ref "C61") (pin "1") (pinfunction "1_1") (pintype "unspecified"))
      (node (ref "C62") (pin "1") (pinfunction "1_1") (pintype "unspecified"))
      (node (ref "C63") (pin "1") (pinfunction "1_1") (pintype "unspecified"))
      (node (ref "C64") (pin "1") (pinfunction "1_1") (pintype "unspecified"))
      (node (ref "C65") (pin "1") (pinfunction "1_1") (pintype "unspecified"))
      (node (ref "C66") (pin "1") (pinfunction "1_1") (pintype "input"))
      (node (ref "C67") (pin "1") (pinfunction "1_1") (pintype "unspecified"))
      (node (ref "C_I2C") (pin "2") (pinfunction "2_2") (pintype "unspecified"))
      (node (ref "C_I2C") (pin "5") (pinfunction "5_5") (pintype "unspecified"))
      (node (ref "C_I2C") (pin "6") (pinfunction "6_6") (pintype "unspecified"))
      (node (ref "C_P0") (pin "2") (pinfunction "2_2") (pintype "unspecified"))
      (node (ref "C_P0") (pin "4") (pinfunction "4_4") (pintype "unspecified"))
      (node (ref "C_P0") (pin "5") (pinfunction "5_5") (pintype "unspecified"))
      (node (ref "C_P1-3") (pin "2") (pinfunction "2_2") (pintype "unspecified"))
      (node (ref "C_P1-3") (pin "6") (pinfunction "6_6") (pintype "unspecified"))
      (node (ref "C_P1-3") (pin "7") (pinfunction "7_7") (pintype "unspecified"))
      (node (ref "C_P4-5") (pin "2") (pinfunction "2_2") (pintype "unspecified"))
      (node (ref "C_P4-5") (pin "5") (pinfunction "5_5") (pintype "unspecified"))
      (node (ref "C_P4-5") (pin "6") (pinfunction "6_6") (pintype "unspecified"))
      (node (ref "D5") (pin "1") (pinfunction "1_1") (pintype "unspecified"))
      (node (ref "FPC1") (pin "11") (pinfunction "11_11") (pintype "unspecified"))
      (node (ref "FPC1") (pin "12") (pinfunction "12_12") (pintype "unspecified"))
      (node (ref "FPC1") (pin "18") (pinfunction "18_18") (pintype "unspecified"))
      (node (ref "FPC1") (pin "19") (pinfunction "19_19") (pintype "unspecified"))
      (node (ref "FPC1") (pin "20") (pinfunction "20_20") (pintype "unspecified"))
      (node (ref "FPC2") (pin "6") (pinfunction "6_6") (pintype "unspecified"))
      (node (ref "FPC2") (pin "7") (pinfunction "7_7") (pintype "unspecified"))
      (node (ref "FPC2") (pin "8") (pinfunction "8_8") (pintype "unspecified"))
      (node (ref "FPC3") (pin "10") (pinfunction "10_10") (pintype "unspecified"))
      (node (ref "FPC3") (pin "23") (pinfunction "23_23") (pintype "unspecified"))
      (node (ref "FPC3") (pin "25") (pinfunction "25_25") (pintype "unspecified"))
      (node (ref "FPC3") (pin "26") (pinfunction "26_26") (pintype "unspecified"))
      (node (ref "HUM") (pin "2") (pinfunction "VSS_2") (pintype "unspecified"))
      (node (ref "HUM") (pin "7") (pinfunction "ep_7") (pintype "unspecified"))
      (node (ref "IND") (pin "1") (pinfunction "K_1") (pintype "unspecified"))
      (node (ref "LS") (pin "3") (pinfunction "GND_3") (pintype "unspecified"))
      (node (ref "PB1") (pin "1") (pinfunction "1_1") (pintype "unspecified"))
      (node (ref "PB1") (pin "3") (pinfunction "3_3") (pintype "unspecified"))
      (node (ref "PB1") (pin "4") (pinfunction "4_4") (pintype "unspecified"))
      (node (ref "PB2") (pin "2") (pinfunction "2_2") (pintype "unspecified"))
      (node (ref "PB2") (pin "3") (pinfunction "3_3") (pintype "unspecified"))
      (node (ref "PB2") (pin "4") (pinfunction "4_4") (pintype "unspecified"))
      (node (ref "PWR") (pin "1") (pinfunction "K_1") (pintype "unspecified"))
      (node (ref "Q4") (pin "2") (pinfunction "E_2") (pintype "unspecified"))
      (node (ref "Q5") (pin "2") (pinfunction "E_2") (pintype "unspecified"))
      (node (ref "R18") (pin "1") (pinfunction "1_1") (pintype "unspecified"))
      (node (ref "R21") (pin "2") (pinfunction "2_2") (pintype "unspecified"))
      (node (ref "R22") (pin "2") (pinfunction "2_2") (pintype "input"))
      (node (ref "R24") (pin "2") (pinfunction "2_2") (pintype "unspecified"))
      (node (ref "R25") (pin "1") (pinfunction "1_1") (pintype "unspecified"))
      (node (ref "R26") (pin "1") (pinfunction "1_1") (pintype "unspecified"))
      (node (ref "R27") (pin "1") (pinfunction "1_1") (pintype "unspecified"))
      (node (ref "R3") (pin "1") (pinfunction "1_1") (pintype "input"))
      (node (ref "R32") (pin "2") (pinfunction "2_2") (pintype "input"))
      (node (ref "R40") (pin "1") (pinfunction "1_1") (pintype "input"))
      (node (ref "R42") (pin "2") (pinfunction "2_2") (pintype "input"))
      (node (ref "R44") (pin "1") (pinfunction "1_1") (pintype "unspecified"))
      (node (ref "R5") (pin "2") (pinfunction "2_2") (pintype "input"))
      (node (ref "RGB1") (pin "2") (pinfunction "GND_2") (pintype "unspecified"))
      (node (ref "RGB2") (pin "2") (pinfunction "GND_2") (pintype "unspecified"))
      (node (ref "RST") (pin "2") (pinfunction "2_2") (pintype "unspecified"))
      (node (ref "SP1") (pin "3") (pinfunction "3_3") (pintype "unspecified"))
      (node (ref "SP1") (pin "4") (pinfunction "4_4") (pintype "unspecified"))
      (node (ref "SW1") (pin "1") (pinfunction "1_1") (pintype "input"))
      (node (ref "SW2") (pin "1") (pinfunction "1_1") (pintype "input"))
      (node (ref "SW3") (pin "1") (pinfunction "1_1") (pintype "input"))
      (node (ref "TF1") (pin "10") (pinfunction "GND_10") (pintype "unspecified"))
      (node (ref "TF1") (pin "11") (pinfunction "GND_11") (pintype "unspecified"))
      (node (ref "TF1") (pin "12") (pinfunction "GND_12") (pintype "unspecified"))
      (node (ref "TF1") (pin "13") (pinfunction "GND_13") (pintype "unspecified"))
      (node (ref "TF1") (pin "6") (pinfunction "VSS_6") (pintype "unspecified"))
      (node (ref "U1") (pin "1") (pinfunction "GND_1") (pintype "unspecified"))
      (node (ref "U1") (pin "40") (pinfunction "GND_40") (pintype "unspecified"))
      (node (ref "U1") (pin "41") (pinfunction "GND_41") (pintype "unspecified"))
      (node (ref "U10") (pin "14") (pinfunction "A0_14") (pintype "unspecified"))
      (node (ref "U10") (pin "6") (pinfunction "GND_6") (pintype "unspecified"))
      (node (ref "U11") (pin "2") (pinfunction "GND_2") (pintype "unspecified"))
      (node (ref "U12") (pin "2") (pinfunction "GND_2") (pintype "unspecified"))
      (node (ref "U13") (pin "7") (pinfunction "GND_7") (pintype "unspecified"))
      (node (ref "U13") (pin "9") (pinfunction "EP_9") (pintype "unspecified"))
      (node (ref "U14") (pin "13") (pinfunction "GNDA_13") (pintype "unspecified"))
      (node (ref "U14") (pin "21") (pinfunction "EP_21") (pintype "unspecified"))
      (node (ref "U14") (pin "4") (pinfunction "GNDD_4") (pintype "unspecified"))
      (node (ref "U14") (pin "8") (pinfunction "AD1_8") (pintype "unspecified"))
      (node (ref "U17") (pin "2") (pinfunction "VSS_2") (pintype "unspecified"))
      (node (ref "U18") (pin "1") (pinfunction "ISO14443LB_1") (pintype "unspecified"))
      (node (ref "U18") (pin "17") (pinfunction "ISO14443LA_17") (pintype "unspecified"))
      (node (ref "U18") (pin "19") (pinfunction "VSS_19") (pintype "unspecified"))
      (node (ref "U18") (pin "21") (pinfunction "EP_21") (pintype "unspecified"))
      (node (ref "U2") (pin "4") (pinfunction "GND_4") (pintype "unspecified"))
      (node (ref "U3") (pin "2") (pinfunction "GND_2") (pintype "input"))
      (node (ref "U4") (pin "1") (pinfunction "CSP_1") (pintype "unspecified"))
      (node (ref "U4") (pin "12") (pinfunction "TEST_12") (pintype "unspecified"))
      (node (ref "U4") (pin "14") (pinfunction "GND_14") (pintype "unspecified"))
      (node (ref "U4") (pin "3") (pinfunction "PGND_3") (pintype "unspecified"))
      (node (ref "U4") (pin "6") (pinfunction "OLIM_6") (pintype "unspecified"))
      (node (ref "U5") (pin "4") (pinfunction "NC_4") (pintype "unspecified"))
      (node (ref "U5") (pin "8") (pinfunction "GNDIO_8") (pintype "unspecified"))
      (node (ref "U5") (pin "9") (pinfunction "GND_9") (pintype "unspecified"))
      (node (ref "U8") (pin "1") (pinfunction "GND_1") (pintype "unspecified"))
      (node (ref "U8") (pin "11") (pinfunction "EP_11") (pintype "unspecified"))
      (node (ref "U8") (pin "2") (pinfunction "GND_2") (pintype "unspecified"))
      (node (ref "U8") (pin "4") (pinfunction "GND_4") (pintype "unspecified"))
      (node (ref "U8") (pin "5") (pinfunction "GND_5") (pintype "unspecified"))
      (node (ref "U8") (pin "6") (pinfunction "GND_6") (pintype "unspecified"))
      (node (ref "U8") (pin "7") (pinfunction "GND_7") (pintype "unspecified"))
      (node (ref "U9") (pin "18") (pinfunction "A0_18") (pintype "unspecified"))
      (node (ref "U9") (pin "23") (pinfunction "A1_23") (pintype "unspecified"))
      (node (ref "U9") (pin "24") (pinfunction "A2_24") (pintype "unspecified"))
      (node (ref "U9") (pin "25") (pinfunction "EP_25") (pintype "unspecified"))
      (node (ref "U9") (pin "9") (pinfunction "GND_9") (pintype "unspecified"))
      (node (ref "USB1") (pin "0") (pinfunction "SH_0") (pintype "unspecified"))
      (node (ref "USB1") (pin "1") (pinfunction "SH_1") (pintype "unspecified"))
      (node (ref "USB1") (pin "2") (pinfunction "SH_2") (pintype "unspecified"))
      (node (ref "USB1") (pin "3") (pinfunction "SH_3") (pintype "unspecified"))
      (node (ref "USB1") (pin "A1") (pinfunction "GND_A1") (pintype "unspecified"))
      (node (ref "USB1") (pin "A12") (pinfunction "GND_A12") (pintype "unspecified"))
      (node (ref "USB1") (pin "B1") (pinfunction "GND_B1") (pintype "unspecified"))
      (node (ref "USB1") (pin "B12") (pinfunction "GND_B12") (pintype "unspecified"))
    )
    (net (code "26") (name "I2S_LRCK") (class "Default")
      (node (ref "U1") (pin "31") (pinfunction "IO38_31") (pintype "unspecified"))
      (node (ref "U13") (pin "2") (pinfunction "LRCLK_2") (pintype "unspecified"))
      (node (ref "U14") (pin "7") (pinfunction "LRCK_7") (pintype "unspecified"))
    )
    (net (code "27") (name "I2S_MCLK") (class "Default")
      (node (ref "U1") (pin "15") (pinfunction "IO3_15") (pintype "unspecified"))
      (node (ref "U14") (pin "20") (pinfunction "MCLK_20") (pintype "unspecified"))
    )
    (net (code "28") (name "I2S_SDI") (class "Default")
      (node (ref "U1") (pin "26") (pinfunction "IO45_26") (pintype "unspecified"))
      (node (ref "U13") (pin "4") (pinfunction "SDATA_4") (pintype "unspecified"))
    )
    (net (code "29") (name "I2S_SDO") (class "Default")
      (node (ref "R21") (pin "1") (pinfunction "1_1") (pintype "unspecified"))
      (node (ref "U1") (pin "32") (pinfunction "IO39_32") (pintype "unspecified"))
      (node (ref "U14") (pin "3") (pinfunction "SDOUT/AD2_3") (pintype "unspecified"))
    )
    (net (code "30") (name "LCD_BLK") (class "Default")
      (node (ref "R19") (pin "2") (pinfunction "2_2") (pintype "input"))
      (node (ref "U9") (pin "1") (pinfunction "P00_1") (pintype "unspecified"))
    )
    (net (code "31") (name "LCD_CS") (class "Default")
      (node (ref "FPC1") (pin "14") (pinfunction "14_14") (pintype "unspecified"))
      (node (ref "U1") (pin "22") (pinfunction "IO14_22") (pintype "unspecified"))
    )
    (net (code "32") (name "LCD_DC") (class "Default")
      (node (ref "FPC1") (pin "15") (pinfunction "15_15") (pintype "unspecified"))
      (node (ref "U1") (pin "21") (pinfunction "IO13_21") (pintype "unspecified"))
    )
    (net (code "33") (name "LCD_MOSI") (class "Default")
      (node (ref "FPC1") (pin "13") (pinfunction "13_13") (pintype "unspecified"))
      (node (ref "U1") (pin "23") (pinfunction "IO21_23") (pintype "unspecified"))
    )
    (net (code "34") (name "LCD_SCLK") (class "Default")
      (node (ref "FPC1") (pin "16") (pinfunction "16_16") (pintype "unspecified"))
      (node (ref "U1") (pin "20") (pinfunction "IO12_20") (pintype "unspecified"))
    )
    (net (code "35") (name "MISO3") (class "Default")
      (node (ref "TF1") (pin "7") (pinfunction "DAT0_7") (pintype "unspecified"))
      (node (ref "U1") (pin "34") (pinfunction "IO41_34") (pintype "unspecified"))
      (node (ref "U2") (pin "2") (pinfunction "SO_2") (pintype "unspecified"))
    )
    (net (code "36") (name "MOSI3") (class "Default")
      (node (ref "TF1") (pin "3") (pinfunction "CMD_3") (pintype "unspecified"))
      (node (ref "U1") (pin "35") (pinfunction "IO42_35") (pintype "unspecified"))
      (node (ref "U2") (pin "5") (pinfunction "SI_5") (pintype "unspecified"))
    )
    (net (code "37") (name "Net-(C25-Pad2)") (class "Default")
      (node (ref "C25") (pin "2") (pinfunction "2_2") (pintype "unspecified"))
      (node (ref "FPC1") (pin "17") (pinfunction "17_17") (pintype "unspecified"))
      (node (ref "R20") (pin "1") (pinfunction "1_1") (pintype "unspecified"))
    )
    (net (code "38") (name "Net-(C68-Pad1)") (class "Default")
      (node (ref "C68") (pin "1") (pinfunction "1_1") (pintype "input"))
      (node (ref "SP1") (pin "1") (pinfunction "1_1") (pintype "unspecified"))
    )
    (net (code "39") (name "Net-(FPC1-Pad5)") (class "Default")
      (node (ref "FPC1") (pin "5") (pinfunction "5_5") (pintype "unspecified"))
      (node (ref "FPC1") (pin "6") (pinfunction "6_6") (pintype "unspecified"))
      (node (ref "FPC1") (pin "7") (pinfunction "7_7") (pintype "unspecified"))
      (node (ref "FPC1") (pin "8") (pinfunction "8_8") (pintype "unspecified"))
      (node (ref "R17") (pin "2") (pinfunction "2_2") (pintype "input"))
    )
    (net (code "40") (name "Net-(FPC3-Pad17)") (class "Default")
      (node (ref "FPC3") (pin "17") (pinfunction "17_17") (pintype "unspecified"))
      (node (ref "R32") (pin "1") (pinfunction "1_1") (pintype "input"))
    )
    (net (code "41") (name "Net-(IND-A)") (class "Default")
      (node (ref "IND") (pin "2") (pinfunction "A_2") (pintype "unspecified"))
      (node (ref "R16") (pin "2") (pinfunction "2_2") (pintype "input"))
    )
    (net (code "42") (name "Net-(LED1-A)") (class "Default")
      (node (ref "LED1") (pin "2") (pinfunction "A_2") (pintype "unspecified"))
      (node (ref "R2") (pin "2") (pinfunction "2_2") (pintype "input"))
    )
    (net (code "43") (name "Net-(LED1-K)") (class "Default")
      (node (ref "LED1") (pin "1") (pinfunction "K_1") (pintype "unspecified"))
      (node (ref "U17") (pin "1") (pinfunction "STAT_1") (pintype "unspecified"))
    )
    (net (code "44") (name "Net-(MIC1-OUT)") (class "Default")
      (node (ref "C27") (pin "2") (pinfunction "2_2") (pintype "input"))
      (node (ref "C6") (pin "2") (pinfunction "2_2") (pintype "input"))
      (node (ref "MIC1") (pin "2") (pinfunction "OUT_2") (pintype "unspecified"))
    )
    (net (code "45") (name "Net-(MIC2-OUT)") (class "Default")
      (node (ref "C38") (pin "2") (pinfunction "2_2") (pintype "input"))
      (node (ref "C40") (pin "2") (pinfunction "2_2") (pintype "input"))
      (node (ref "MIC2") (pin "2") (pinfunction "OUT_2") (pintype "unspecified"))
    )
    (net (code "46") (name "Net-(PWR-A)") (class "Default")
      (node (ref "PWR") (pin "2") (pinfunction "A_2") (pintype "unspecified"))
      (node (ref "R15") (pin "1") (pinfunction "1_1") (pintype "input"))
    )
    (net (code "47") (name "Net-(Q2-G)") (class "Default")
      (node (ref "D6") (pin "2") (pinfunction "2_2") (pintype "unspecified"))
      (node (ref "Q2") (pin "1") (pinfunction "G_1") (pintype "unspecified"))
      (node (ref "Q3") (pin "3") (pinfunction "C2_3") (pintype "unspecified"))
      (node (ref "R26") (pin "2") (pinfunction "2_2") (pintype "unspecified"))
    )
    (net (code "48") (name "Net-(Q3-B1)") (class "Default")
      (node (ref "Q3") (pin "2") (pinfunction "B1_2") (pintype "unspecified"))
      (node (ref "Q3") (pin "5") (pinfunction "B2_5") (pintype "unspecified"))
      (node (ref "Q3") (pin "6") (pinfunction "C1_6") (pintype "unspecified"))
      (node (ref "R25") (pin "2") (pinfunction "2_2") (pintype "unspecified"))
    )
    (net (code "49") (name "Net-(Q4-B)") (class "Default")
      (node (ref "Q4") (pin "1") (pinfunction "B_1") (pintype "unspecified"))
      (node (ref "R18") (pin "2") (pinfunction "2_2") (pintype "unspecified"))
      (node (ref "R19") (pin "1") (pinfunction "1_1") (pintype "input"))
    )
    (net (code "50") (name "Net-(Q4-C)") (class "Default")
      (node (ref "Q4") (pin "3") (pinfunction "C_3") (pintype "unspecified"))
      (node (ref "R17") (pin "1") (pinfunction "1_1") (pintype "input"))
    )
    (net (code "51") (name "Net-(Q5-B)") (class "Default")
      (node (ref "Q5") (pin "1") (pinfunction "B_1") (pintype "unspecified"))
      (node (ref "R27") (pin "2") (pinfunction "2_2") (pintype "unspecified"))
      (node (ref "R28") (pin "1") (pinfunction "1_1") (pintype "unspecified"))
    )
    (net (code "52") (name "Net-(Q5-C)") (class "Default")
      (node (ref "Q5") (pin "3") (pinfunction "C_3") (pintype "unspecified"))
      (node (ref "R29") (pin "1") (pinfunction "1_1") (pintype "unspecified"))
      (node (ref "U2") (pin "1") (pinfunction "CS#_1") (pintype "unspecified"))
    )
    (net (code "53") (name "Net-(R41-Pad2)") (class "Default")
      (node (ref "R41") (pin "2") (pinfunction "2_2") (pintype "input"))
      (node (ref "R42") (pin "1") (pinfunction "1_1") (pintype "input"))
    )
    (net (code "54") (name "Net-(RGB1-DOUT)") (class "Default")
      (node (ref "RGB1") (pin "1") (pinfunction "DOUT_1") (pintype "unspecified"))
      (node (ref "RGB2") (pin "3") (pinfunction "DIN_3") (pintype "unspecified"))
    )
    (net (code "55") (name "Net-(U2-HOLD#)") (class "Default")
      (node (ref "R31") (pin "2") (pinfunction "2_2") (pintype "unspecified"))
      (node (ref "U2") (pin "7") (pinfunction "HOLD#_7") (pintype "unspecified"))
    )
    (net (code "56") (name "Net-(U4-BST1)") (class "Default")
      (node (ref "C57") (pin "1") (pinfunction "1_1") (pintype "unspecified"))
      (node (ref "U4") (pin "8") (pinfunction "BST1_8") (pintype "unspecified"))
    )
    (net (code "57") (name "Net-(U4-BST2)") (class "Default")
      (node (ref "C56") (pin "1") (pinfunction "1_1") (pintype "unspecified"))
      (node (ref "U4") (pin "11") (pinfunction "BST2_11") (pintype "unspecified"))
    )
    (net (code "58") (name "Net-(U4-FB)") (class "Default")
      (node (ref "R23") (pin "1") (pinfunction "1_1") (pintype "input"))
      (node (ref "R24") (pin "1") (pinfunction "1_1") (pintype "unspecified"))
      (node (ref "U4") (pin "5") (pinfunction "FB_5") (pintype "unspecified"))
    )
    (net (code "59") (name "Net-(U4-SW1)") (class "Default")
      (node (ref "C57") (pin "2") (pinfunction "2_2") (pintype "unspecified"))
      (node (ref "L1") (pin "2") (pinfunction "2_2") (pintype "unspecified"))
      (node (ref "U4") (pin "9") (pinfunction "SW1_9") (pintype "unspecified"))
    )
    (net (code "60") (name "Net-(U4-SW2)") (class "Default")
      (node (ref "C56") (pin "2") (pinfunction "2_2") (pintype "unspecified"))
      (node (ref "L1") (pin "1") (pinfunction "1_1") (pintype "unspecified"))
      (node (ref "U4") (pin "10") (pinfunction "SW2_10") (pintype "unspecified"))
    )
    (net (code "61") (name "Net-(U13-VON)") (class "Default")
      (node (ref "C68") (pin "2") (pinfunction "2_2") (pintype "input"))
      (node (ref "U13") (pin "5") (pinfunction "VON_5") (pintype "unspecified"))
    )
    (net (code "62") (name "Net-(U13-VOP)") (class "Default")
      (node (ref "SP1") (pin "2") (pinfunction "2_2") (pintype "unspecified"))
      (node (ref "U13") (pin "8") (pinfunction "VOP_8") (pintype "unspecified"))
    )
    (net (code "63") (name "Net-(U14-AINLN)") (class "Default")
      (node (ref "C28") (pin "1") (pinfunction "1_1") (pintype "input"))
      (node (ref "U14") (pin "10") (pinfunction "AINLN_10") (pintype "unspecified"))
    )
    (net (code "64") (name "Net-(U14-AINLP)") (class "Default")
      (node (ref "C27") (pin "1") (pinfunction "1_1") (pintype "input"))
      (node (ref "U14") (pin "9") (pinfunction "AINLP_9") (pintype "unspecified"))
    )
    (net (code "65") (name "Net-(U14-AINRN)") (class "Default")
      (node (ref "C39") (pin "1") (pinfunction "1_1") (pintype "input"))
      (node (ref "U14") (pin "15") (pinfunction "AINRN_15") (pintype "unspecified"))
    )
    (net (code "66") (name "Net-(U14-AINRP)") (class "Default")
      (node (ref "C38") (pin "1") (pinfunction "1_1") (pintype "input"))
      (node (ref "U14") (pin "16") (pinfunction "AINRP_16") (pintype "unspecified"))
    )
    (net (code "67") (name "Net-(U14-REFP)") (class "Default")
      (node (ref "C43") (pin "2") (pinfunction "2_2") (pintype "input"))
      (node (ref "U14") (pin "14") (pinfunction "REFP_14") (pintype "unspecified"))
    )
    (net (code "68") (name "Net-(U14-REFQ)") (class "Default")
      (node (ref "C42") (pin "2") (pinfunction "2_2") (pintype "input"))
      (node (ref "U14") (pin "11") (pinfunction "REFQ_11") (pintype "unspecified"))
    )
    (net (code "69") (name "Net-(U17-PROG)") (class "Default")
      (node (ref "R40") (pin "2") (pinfunction "2_2") (pintype "input"))
      (node (ref "R41") (pin "1") (pinfunction "1_1") (pintype "input"))
      (node (ref "U17") (pin "5") (pinfunction "PROG_5") (pintype "unspecified"))
    )
    (net (code "70") (name "Net-(U18-ENA)") (class "Default")
      (node (ref "R43") (pin "1") (pinfunction "1_1") (pintype "unspecified"))
      (node (ref "U18") (pin "11") (pinfunction "ENA_11") (pintype "unspecified"))
    )
    (net (code "71") (name "Net-(U18-VCC)") (class "Default")
      (node (ref "C67") (pin "2") (pinfunction "2_2") (pintype "unspecified"))
      (node (ref "U18") (pin "15") (pinfunction "VOUT_15") (pintype "unspecified"))
      (node (ref "U18") (pin "18") (pinfunction "VCC_18") (pintype "unspecified"))
    )
    (net (code "72") (name "P0") (class "Default")
      (node (ref "C_P0") (pin "3") (pinfunction "3_3") (pintype "unspecified"))
      (node (ref "U1") (pin "39") (pinfunction "IO1_39") (pintype "unspecified"))
    )
    (net (code "73") (name "P1") (class "Default")
      (node (ref "C_P1-3") (pin "3") (pinfunction "3_3") (pintype "unspecified"))
      (node (ref "U9") (pin "8") (pinfunction "P07_8") (pintype "unspecified"))
    )
    (net (code "74") (name "P2") (class "Default")
      (node (ref "C_P1-3") (pin "4") (pinfunction "4_4") (pintype "unspecified"))
      (node (ref "U9") (pin "16") (pinfunction "P16_16") (pintype "unspecified"))
    )
    (net (code "75") (name "P3") (class "Default")
      (node (ref "C_P1-3") (pin "5") (pinfunction "5_5") (pintype "unspecified"))
      (node (ref "U9") (pin "15") (pinfunction "P15_15") (pintype "unspecified"))
    )
    (net (code "76") (name "P4") (class "Default")
      (node (ref "C_P4-5") (pin "3") (pinfunction "3_3") (pintype "unspecified"))
      (node (ref "U9") (pin "14") (pinfunction "P14_14") (pintype "unspecified"))
    )
    (net (code "77") (name "P5") (class "Default")
      (node (ref "C_P4-5") (pin "4") (pinfunction "4_4") (pintype "unspecified"))
      (node (ref "U9") (pin "13") (pinfunction "P13_13") (pintype "unspecified"))
    )
    (net (code "78") (name "P6") (class "Default")
      (node (ref "R44") (pin "2") (pinfunction "2_2") (pintype "unspecified"))
      (node (ref "U13") (pin "1") (pinfunction "CTRL_1") (pintype "unspecified"))
      (node (ref "U9") (pin "10") (pinfunction "P10_10") (pintype "unspecified"))
    )
    (net (code "79") (name "P7") (class "Default")
      (node (ref "R39") (pin "1") (pinfunction "1_1") (pintype "unspecified"))
      (node (ref "SW3") (pin "2") (pinfunction "2_2") (pintype "input"))
      (node (ref "U9") (pin "11") (pinfunction "P11_11") (pintype "unspecified"))
    )
    (net (code "80") (name "P8") (class "Default")
      (node (ref "R37") (pin "1") (pinfunction "1_1") (pintype "unspecified"))
      (node (ref "SW1") (pin "2") (pinfunction "2_2") (pintype "input"))
      (node (ref "U9") (pin "12") (pinfunction "P12_12") (pintype "unspecified"))
    )
    (net (code "81") (name "P9") (class "Default")
      (node (ref "R38") (pin "1") (pinfunction "1_1") (pintype "unspecified"))
      (node (ref "SW2") (pin "2") (pinfunction "2_2") (pintype "input"))
      (node (ref "U9") (pin "5") (pinfunction "P04_5") (pintype "unspecified"))
    )
    (net (code "82") (name "P10") (class "Default")
      (node (ref "C21") (pin "2") (pinfunction "2_2") (pintype "unspecified"))
      (node (ref "PB1") (pin "2") (pinfunction "2_2") (pintype "unspecified"))
      (node (ref "R7") (pin "1") (pinfunction "1_1") (pintype "unspecified"))
      (node (ref "U9") (pin "6") (pinfunction "P05_6") (pintype "unspecified"))
    )
    (net (code "83") (name "P11") (class "Default")
      (node (ref "C20") (pin "2") (pinfunction "2_2") (pintype "unspecified"))
      (node (ref "PB2") (pin "1") (pinfunction "1_1") (pintype "unspecified"))
      (node (ref "R6") (pin "1") (pinfunction "1_1") (pintype "unspecified"))
      (node (ref "U9") (pin "7") (pinfunction "P06_7") (pintype "unspecified"))
    )
    (net (code "84") (name "RGB") (class "Default")
      (node (ref "RGB1") (pin "3") (pinfunction "DIN_3") (pintype "unspecified"))
      (node (ref "U1") (pin "16") (pinfunction "IO46_16") (pintype "unspecified"))
    )
    (net (code "85") (name "RST") (class "Default")
      (node (ref "C3") (pin "2") (pinfunction "2_2") (pintype "input"))
      (node (ref "R1") (pin "1") (pinfunction "1_1") (pintype "unspecified"))
      (node (ref "RST") (pin "1") (pinfunction "1_1") (pintype "unspecified"))
      (node (ref "U1") (pin "3") (pinfunction "EN_3") (pintype "unspecified"))
    )
    (net (code "86") (name "SCL") (class "Default")
      (node (ref "C_I2C") (pin "3") (pinfunction "3_3") (pintype "unspecified"))
      (node (ref "FPC2") (pin "3") (pinfunction "3_3") (pintype "unspecified"))
      (node (ref "FPC3") (pin "20") (pinfunction "20_20") (pintype "unspecified"))
      (node (ref "HUM") (pin "6") (pinfunction "SCL_6") (pintype "unspecified"))
      (node (ref "LS") (pin "4") (pinfunction "SCL_4") (pintype "unspecified"))
      (node (ref "R13") (pin "1") (pinfunction "1_1") (pintype "unspecified"))
      (node (ref "R34") (pin "1") (pinfunction "1_1") (pintype "unspecified"))
      (node (ref "R36") (pin "1") (pinfunction "1_1") (pintype "unspecified"))
      (node (ref "U1") (pin "25") (pinfunction "IO48_25") (pintype "unspecified"))
      (node (ref "U10") (pin "12") (pinfunction "SCL_12") (pintype "unspecified"))
      (node (ref "U14") (pin "19") (pinfunction "CCLK_19") (pintype "unspecified"))
      (node (ref "U18") (pin "10") (pinfunction "l2C_SCL_10") (pintype "unspecified"))
      (node (ref "U5") (pin "12") (pinfunction "SCx_12") (pintype "unspecified"))
      (node (ref "U8") (pin "8") (pinfunction "SCL_8") (pintype "unspecified"))
      (node (ref "U9") (pin "19") (pinfunction "SCL_19") (pintype "unspecified"))
    )
    (net (code "87") (name "SCLK3") (class "Default")
      (node (ref "TF1") (pin "5") (pinfunction "CLK_5") (pintype "unspecified"))
      (node (ref "U1") (pin "36") (pinfunction "RXD0_36") (pintype "unspecified"))
      (node (ref "U2") (pin "6") (pinfunction "SCLK_6") (pintype "unspecified"))
    )
    (net (code "88") (name "SDA") (class "Default")
      (node (ref "C_I2C") (pin "4") (pinfunction "4_4") (pintype "unspecified"))
      (node (ref "FPC2") (pin "2") (pinfunction "2_2") (pintype "unspecified"))
      (node (ref "FPC3") (pin "22") (pinfunction "22_22") (pintype "unspecified"))
      (node (ref "HUM") (pin "1") (pinfunction "SDA_1") (pintype "unspecified"))
      (node (ref "LS") (pin "6") (pinfunction "SDA_6") (pintype "unspecified"))
      (node (ref "R12") (pin "2") (pinfunction "2_2") (pintype "unspecified"))
      (node (ref "R33") (pin "2") (pinfunction "2_2") (pintype "unspecified"))
      (node (ref "R35") (pin "2") (pinfunction "2_2") (pintype "unspecified"))
      (node (ref "U1") (pin "24") (pinfunction "IO47_24") (pintype "unspecified"))
      (node (ref "U10") (pin "11") (pinfunction "SDA_11") (pintype "unspecified"))
      (node (ref "U14") (pin "18") (pinfunction "CDATA_18") (pintype "unspecified"))
      (node (ref "U18") (pin "9") (pinfunction "l2C_SDA_9") (pintype "unspecified"))
      (node (ref "U5") (pin "2") (pinfunction "SDx_2") (pintype "unspecified"))
      (node (ref "U8") (pin "3") (pinfunction "SDA_3") (pintype "unspecified"))
      (node (ref "U9") (pin "20") (pinfunction "DA_20") (pintype "unspecified"))
    )
    (net (code "89") (name "SE_RST") (class "Default")
      (node (ref "U18") (pin "14") (pinfunction "ISO7816RST_N_14") (pintype "unspecified"))
      (node (ref "U8") (pin "9") (pinfunction "RST_9") (pintype "unspecified"))
      (node (ref "U9") (pin "4") (pinfunction "P03_4") (pintype "unspecified"))
    )
    (net (code "90") (name "TS_INT") (class "Default")
      (node (ref "FPC2") (pin "4") (pinfunction "4_4") (pintype "unspecified"))
      (node (ref "U1") (pin "38") (pinfunction "IO2_38") (pintype "unspecified"))
      (node (ref "U10") (pin "10") (pinfunction "PENIRQ_10") (pintype "unspecified"))
    )
    (net (code "91") (name "TS_RST") (class "Default")
      (node (ref "FPC2") (pin "5") (pinfunction "5_5") (pintype "unspecified"))
      (node (ref "U9") (pin "2") (pinfunction "P01_2") (pintype "unspecified"))
    )
    (net (code "92") (name "U_LED") (class "Default")
      (node (ref "R16") (pin "1") (pinfunction "1_1") (pintype "input"))
      (node (ref "U9") (pin "17") (pinfunction "P17_17") (pintype "unspecified"))
    )
    (net (code "93") (name "VBAT") (class "Default")
      (node (ref "BAT1") (pin "2") (pinfunction "2_2") (pintype "unspecified"))
      (node (ref "C66") (pin "2") (pinfunction "2_2") (pintype "input"))
      (node (ref "D5") (pin "2") (pinfunction "2_2") (pintype "unspecified"))
      (node (ref "Q2") (pin "3") (pinfunction "D_3") (pintype "unspecified"))
      (node (ref "Q3") (pin "1") (pinfunction "E1_1") (pintype "unspecified"))
      (node (ref "U17") (pin "3") (pinfunction "VBAT_3") (pintype "unspecified"))
    )
    (net (code "94") (name "VBUS") (class "Default")
      (node (ref "D2") (pin "2") (pinfunction "A_2") (pintype "unspecified"))
      (node (ref "R2") (pin "1") (pinfunction "1_1") (pintype "input"))
      (node (ref "U17") (pin "4") (pinfunction "VDD_4") (pintype "unspecified"))
      (node (ref "USB1") (pin "A4") (pinfunction "VBUS_A4") (pintype "unspecified"))
      (node (ref "USB1") (pin "A9") (pinfunction "VBUS_A9") (pintype "unspecified"))
      (node (ref "USB1") (pin "B4") (pinfunction "VBUS_B4") (pintype "unspecified"))
      (node (ref "USB1") (pin "B9") (pinfunction "VBUS_B9") (pintype "unspecified"))
    )
    (net (code "95") (name "VCC") (class "Default")
      (node (ref "C51") (pin "2") (pinfunction "2_2") (pintype "unspecified"))
      (node (ref "C52") (pin "2") (pinfunction "2_2") (pintype "unspecified"))
      (node (ref "C58") (pin "2") (pinfunction "2_2") (pintype "unspecified"))
      (node (ref "D2") (pin "1") (pinfunction "K_1") (pintype "unspecified"))
      (node (ref "D6") (pin "1") (pinfunction "1_1") (pintype "unspecified"))
      (node (ref "Q2") (pin "2") (pinfunction "S_2") (pintype "unspecified"))
      (node (ref "Q3") (pin "4") (pinfunction "E2_4") (pintype "unspecified"))
      (node (ref "U4") (pin "2") (pinfunction "VIN_2") (pintype "unspecified"))
      (node (ref "U4") (pin "7") (pinfunction "EN_7") (pintype "unspecified"))
    )
    (net (code "96") (name "VLDO") (class "Default")
      (node (ref "C54") (pin "1") (pinfunction "1_1") (pintype "unspecified"))
      (node (ref "U4") (pin "13") (pinfunction "VCC_13") (pintype "unspecified"))
      (node (ref "U4") (pin "15") (pinfunction "CSN_15") (pintype "unspecified"))
    )
    (net (code "97") (name "X+") (class "Default")
      (node (ref "FPC1") (pin "4") (pinfunction "4_4") (pintype "unspecified"))
      (node (ref "U10") (pin "2") (pinfunction "X+_2") (pintype "unspecified"))
    )
    (net (code "98") (name "X-") (class "Default")
      (node (ref "FPC1") (pin "2") (pinfunction "2_2") (pintype "unspecified"))
      (node (ref "U10") (pin "4") (pinfunction "X-_4") (pintype "unspecified"))
    )
    (net (code "99") (name "Y+") (class "Default")
      (node (ref "FPC1") (pin "3") (pinfunction "3_3") (pintype "unspecified"))
      (node (ref "U10") (pin "3") (pinfunction "Y+_3") (pintype "unspecified"))
    )
    (net (code "100") (name "Y-") (class "Default")
      (node (ref "FPC1") (pin "1") (pinfunction "1_1") (pintype "unspecified"))
      (node (ref "U10") (pin "5") (pinfunction "Y-_5") (pintype "unspecified"))
    )
    (net (code "101") (name "unconnected-(BATT1-Pad1)") (class "Default")
      (node (ref "BATT1") (pin "1") (pinfunction "1_1") (pintype "unspecified"))
    )
    (net (code "102") (name "unconnected-(BATT1-Pad2)") (class "Default")
      (node (ref "BATT1") (pin "2") (pinfunction "2_2") (pintype "unspecified"))
    )
    (net (code "103") (name "unconnected-(BATT1-Pad3)") (class "Default")
      (node (ref "BATT1") (pin "3") (pinfunction "3_3") (pintype "unspecified"))
    )
    (net (code "104") (name "unconnected-(BATT1-Pad4)") (class "Default")
      (node (ref "BATT1") (pin "4") (pinfunction "4_4") (pintype "unspecified"))
    )
    (net (code "105") (name "unconnected-(CN2-Pad1)") (class "Default")
      (node (ref "CN2") (pin "1") (pinfunction "1_1") (pintype "unspecified"))
    )
    (net (code "106") (name "unconnected-(CN2-Pad2)") (class "Default")
      (node (ref "CN2") (pin "2") (pinfunction "2_2") (pintype "unspecified"))
    )
    (net (code "107") (name "unconnected-(CN2-Pad3)") (class "Default")
      (node (ref "CN2") (pin "3") (pinfunction "3_3") (pintype "unspecified"))
    )
    (net (code "108") (name "unconnected-(CN2-Pad4)") (class "Default")
      (node (ref "CN2") (pin "4") (pinfunction "4_4") (pintype "unspecified"))
    )
    (net (code "109") (name "unconnected-(FPC3-Pad1)") (class "Default")
      (node (ref "FPC3") (pin "1") (pinfunction "1_1") (pintype "unspecified"))
    )
    (net (code "110") (name "unconnected-(FPC3-Pad2)") (class "Default")
      (node (ref "FPC3") (pin "2") (pinfunction "2_2") (pintype "unspecified"))
    )
    (net (code "111") (name "unconnected-(FPC3-Pad24)") (class "Default")
      (node (ref "FPC3") (pin "24") (pinfunction "24_24") (pintype "unspecified"))
    )
    (net (code "112") (name "unconnected-(HUM-NC-Pad3)") (class "Default")
      (node (ref "HUM") (pin "3") (pinfunction "NC_3") (pintype "unspecified"))
    )
    (net (code "113") (name "unconnected-(HUM-NC-Pad4)") (class "Default")
      (node (ref "HUM") (pin "4") (pinfunction "NC_4") (pintype "unspecified"))
    )
    (net (code "114") (name "unconnected-(HUM1-GND-Pad5)") (class "Default")
      (node (ref "HUM1") (pin "5") (pinfunction "GND_5") (pintype "unspecified"))
    )
    (net (code "115") (name "unconnected-(HUM1-NC-Pad1)") (class "Default")
      (node (ref "HUM1") (pin "1") (pinfunction "NC_1") (pintype "unspecified"))
    )
    (net (code "116") (name "unconnected-(HUM1-NC-Pad6)") (class "Default")
      (node (ref "HUM1") (pin "6") (pinfunction "NC_6") (pintype "unspecified"))
    )
    (net (code "117") (name "unconnected-(HUM1-SCL-Pad3)") (class "Default")
      (node (ref "HUM1") (pin "3") (pinfunction "SCL_3") (pintype "unspecified"))
    )
    (net (code "118") (name "unconnected-(HUM1-SDA-Pad4)") (class "Default")
      (node (ref "HUM1") (pin "4") (pinfunction "SDA_4") (pintype "unspecified"))
    )
    (net (code "119") (name "unconnected-(HUM1-VDD-Pad2)") (class "Default")
      (node (ref "HUM1") (pin "2") (pinfunction "VDD_2") (pintype "unspecified"))
    )
    (net (code "120") (name "unconnected-(LS-INT-Pad5)") (class "Default")
      (node (ref "LS") (pin "5") (pinfunction "INT_5") (pintype "unspecified"))
    )
    (net (code "121") (name "unconnected-(LS-NC-Pad2)") (class "Default")
      (node (ref "LS") (pin "2") (pinfunction "NC_2") (pintype "unspecified"))
    )
    (net (code "122") (name "unconnected-(RGB2-DOUT-Pad1)") (class "Default")
      (node (ref "RGB2") (pin "1") (pinfunction "DOUT_1") (pintype "unspecified"))
    )
    (net (code "123") (name "unconnected-(SW4-Pad1)") (class "Default")
      (node (ref "SW4") (pin "1") (pinfunction "1_1") (pintype "input"))
    )
    (net (code "124") (name "unconnected-(SW4-Pad2)") (class "Default")
      (node (ref "SW4") (pin "2") (pinfunction "2_2") (pintype "input"))
    )
    (net (code "125") (name "unconnected-(SW4-Pad3)") (class "Default")
      (node (ref "SW4") (pin "3") (pinfunction "3_3") (pintype "input"))
    )
    (net (code "126") (name "unconnected-(SW4-Pad4)") (class "Default")
      (node (ref "SW4") (pin "4") (pinfunction "4_4") (pintype "input"))
    )
    (net (code "127") (name "unconnected-(SW5-Pad1)") (class "Default")
      (node (ref "SW5") (pin "1") (pinfunction "1_1") (pintype "input"))
    )
    (net (code "128") (name "unconnected-(SW5-Pad2)") (class "Default")
      (node (ref "SW5") (pin "2") (pinfunction "2_2") (pintype "input"))
    )
    (net (code "129") (name "unconnected-(SW5-Pad3)") (class "Default")
      (node (ref "SW5") (pin "3") (pinfunction "3_3") (pintype "input"))
    )
    (net (code "130") (name "unconnected-(SW5-Pad4)") (class "Default")
      (node (ref "SW5") (pin "4") (pinfunction "4_4") (pintype "input"))
    )
    (net (code "131") (name "unconnected-(SW6-Pad1)") (class "Default")
      (node (ref "SW6") (pin "1") (pinfunction "1_1") (pintype "input"))
    )
    (net (code "132") (name "unconnected-(SW6-Pad2)") (class "Default")
      (node (ref "SW6") (pin "2") (pinfunction "2_2") (pintype "input"))
    )
    (net (code "133") (name "unconnected-(SW6-Pad3)") (class "Default")
      (node (ref "SW6") (pin "3") (pinfunction "3_3") (pintype "input"))
    )
    (net (code "134") (name "unconnected-(SW6-Pad4)") (class "Default")
      (node (ref "SW6") (pin "4") (pinfunction "4_4") (pintype "input"))
    )
    (net (code "135") (name "unconnected-(TF1-CD-Pad9)") (class "Default")
      (node (ref "TF1") (pin "9") (pinfunction "CD_9") (pintype "unspecified"))
    )
    (net (code "136") (name "unconnected-(TF1-DAT1-Pad8)") (class "Default")
      (node (ref "TF1") (pin "8") (pinfunction "DAT1_8") (pintype "unspecified"))
    )
    (net (code "137") (name "unconnected-(TF1-DAT2-Pad1)") (class "Default")
      (node (ref "TF1") (pin "1") (pinfunction "DAT2_1") (pintype "unspecified"))
    )
    (net (code "138") (name "unconnected-(U1-IO35-Pad28)") (class "Default")
      (node (ref "U1") (pin "28") (pinfunction "IO35_28") (pintype "unspecified"))
    )
    (net (code "139") (name "unconnected-(U1-IO36-Pad29)") (class "Default")
      (node (ref "U1") (pin "29") (pinfunction "IO36_29") (pintype "unspecified"))
    )
    (net (code "140") (name "unconnected-(U1-IO37-Pad30)") (class "Default")
      (node (ref "U1") (pin "30") (pinfunction "IO37_30") (pintype "unspecified"))
    )
    (net (code "141") (name "unconnected-(U2-NC-Pad3)") (class "Default")
      (node (ref "U2") (pin "3") (pinfunction "NC_3") (pintype "unspecified"))
    )
    (net (code "142") (name "unconnected-(U3-NC-Pad5)") (class "Default")
      (node (ref "U3") (pin "5") (pinfunction "NC_5") (pintype "input"))
    )
    (net (code "143") (name "unconnected-(U5-CS-Pad10)") (class "Default")
      (node (ref "U5") (pin "10") (pinfunction "CS_10") (pintype "unspecified"))
    )
    (net (code "144") (name "unconnected-(U5-INT1-Pad5)") (class "Default")
      (node (ref "U5") (pin "5") (pinfunction "INT1_5") (pintype "unspecified"))
    )
    (net (code "145") (name "unconnected-(U5-INT2-Pad6)") (class "Default")
      (node (ref "U5") (pin "6") (pinfunction "INT2_6") (pintype "unspecified"))
    )
    (net (code "146") (name "unconnected-(U5-NC-Pad11)") (class "Default")
      (node (ref "U5") (pin "11") (pinfunction "NC_11") (pintype "unspecified"))
    )
    (net (code "147") (name "unconnected-(U5-SDO-Pad1)") (class "Default")
      (node (ref "U5") (pin "1") (pinfunction "SDO_1") (pintype "unspecified"))
    )
    (net (code "148") (name "unconnected-(U10-AUX-Pad16)") (class "Default")
      (node (ref "U10") (pin "16") (pinfunction "AUX_16") (pintype "unspecified"))
    )
    (net (code "149") (name "unconnected-(U10-NC-Pad9)") (class "Default")
      (node (ref "U10") (pin "9") (pinfunction "NC_9") (pintype "unspecified"))
    )
    (net (code "150") (name "unconnected-(U10-NC{slash}2-Pad7)") (class "Default")
      (node (ref "U10") (pin "7") (pinfunction "NC/2_7") (pintype "unspecified"))
    )
    (net (code "151") (name "unconnected-(U10-NC{slash}3-Pad15)") (class "Default")
      (node (ref "U10") (pin "15") (pinfunction "NC/3_15") (pintype "unspecified"))
    )
    (net (code "152") (name "unconnected-(U10-NC{slash}4-Pad8)") (class "Default")
      (node (ref "U10") (pin "8") (pinfunction "NC/4_8") (pintype "unspecified"))
    )
    (net (code "153") (name "unconnected-(U11-NC-Pad4)") (class "Default")
      (node (ref "U11") (pin "4") (pinfunction "NC_4") (pintype "unspecified"))
    )
    (net (code "154") (name "unconnected-(U12-NC-Pad4)") (class "Default")
      (node (ref "U12") (pin "4") (pinfunction "NC_4") (pintype "unspecified"))
    )
    (net (code "155") (name "unconnected-(U14-TDMIN-Pad2)") (class "Default")
      (node (ref "U14") (pin "2") (pinfunction "TDMIN_2") (pintype "unspecified"))
    )
    (net (code "156") (name "unconnected-(U18-ISO7816CLK-Pad13)") (class "Default")
      (node (ref "U18") (pin "13") (pinfunction "ISO7816CLK_13") (pintype "unspecified"))
    )
    (net (code "157") (name "unconnected-(U18-ISO7816IO1-Pad3)") (class "Default")
      (node (ref "U18") (pin "3") (pinfunction "ISO7816IO1_3") (pintype "unspecified"))
    )
    (net (code "158") (name "unconnected-(U18-ISO7816IO2-Pad16)") (class "Default")
      (node (ref "U18") (pin "16") (pinfunction "ISO7816IO2_16") (pintype "unspecified"))
    )
    (net (code "159") (name "unconnected-(U18-n.c.-Pad2)") (class "Default")
      (node (ref "U18") (pin "2") (pinfunction "n.c._2") (pintype "unspecified"))
    )
    (net (code "160") (name "unconnected-(U18-n.c.-Pad4)") (class "Default")
      (node (ref "U18") (pin "4") (pinfunction "n.c._4") (pintype "unspecified"))
    )
    (net (code "161") (name "unconnected-(U18-n.c.-Pad5)") (class "Default")
      (node (ref "U18") (pin "5") (pinfunction "n.c._5") (pintype "unspecified"))
    )
    (net (code "162") (name "unconnected-(U18-n.c.-Pad6)") (class "Default")
      (node (ref "U18") (pin "6") (pinfunction "n.c._6") (pintype "unspecified"))
    )
    (net (code "163") (name "unconnected-(U18-n.c.-Pad7)") (class "Default")
      (node (ref "U18") (pin "7") (pinfunction "n.c._7") (pintype "unspecified"))
    )
    (net (code "164") (name "unconnected-(U18-n.c.-Pad8)") (class "Default")
      (node (ref "U18") (pin "8") (pinfunction "n.c._8") (pintype "unspecified"))
    )
    (net (code "165") (name "unconnected-(U18-n.c.-Pad20)") (class "Default")
      (node (ref "U18") (pin "20") (pinfunction "n.c._20") (pintype "unspecified"))
    )
    (net (code "166") (name "unconnected-(USB1-SBU1-PadA8)") (class "Default")
      (node (ref "USB1") (pin "A8") (pinfunction "SBU1_A8") (pintype "unspecified"))
    )
    (net (code "167") (name "unconnected-(USB1-SBU2-PadB8)") (class "Default")
      (node (ref "USB1") (pin "B8") (pinfunction "SBU2_B8") (pintype "unspecified"))
    )
  )
)
